# BlackIce_11_10_17.net
KiCad netlist of a schematic drawn in EAGLE
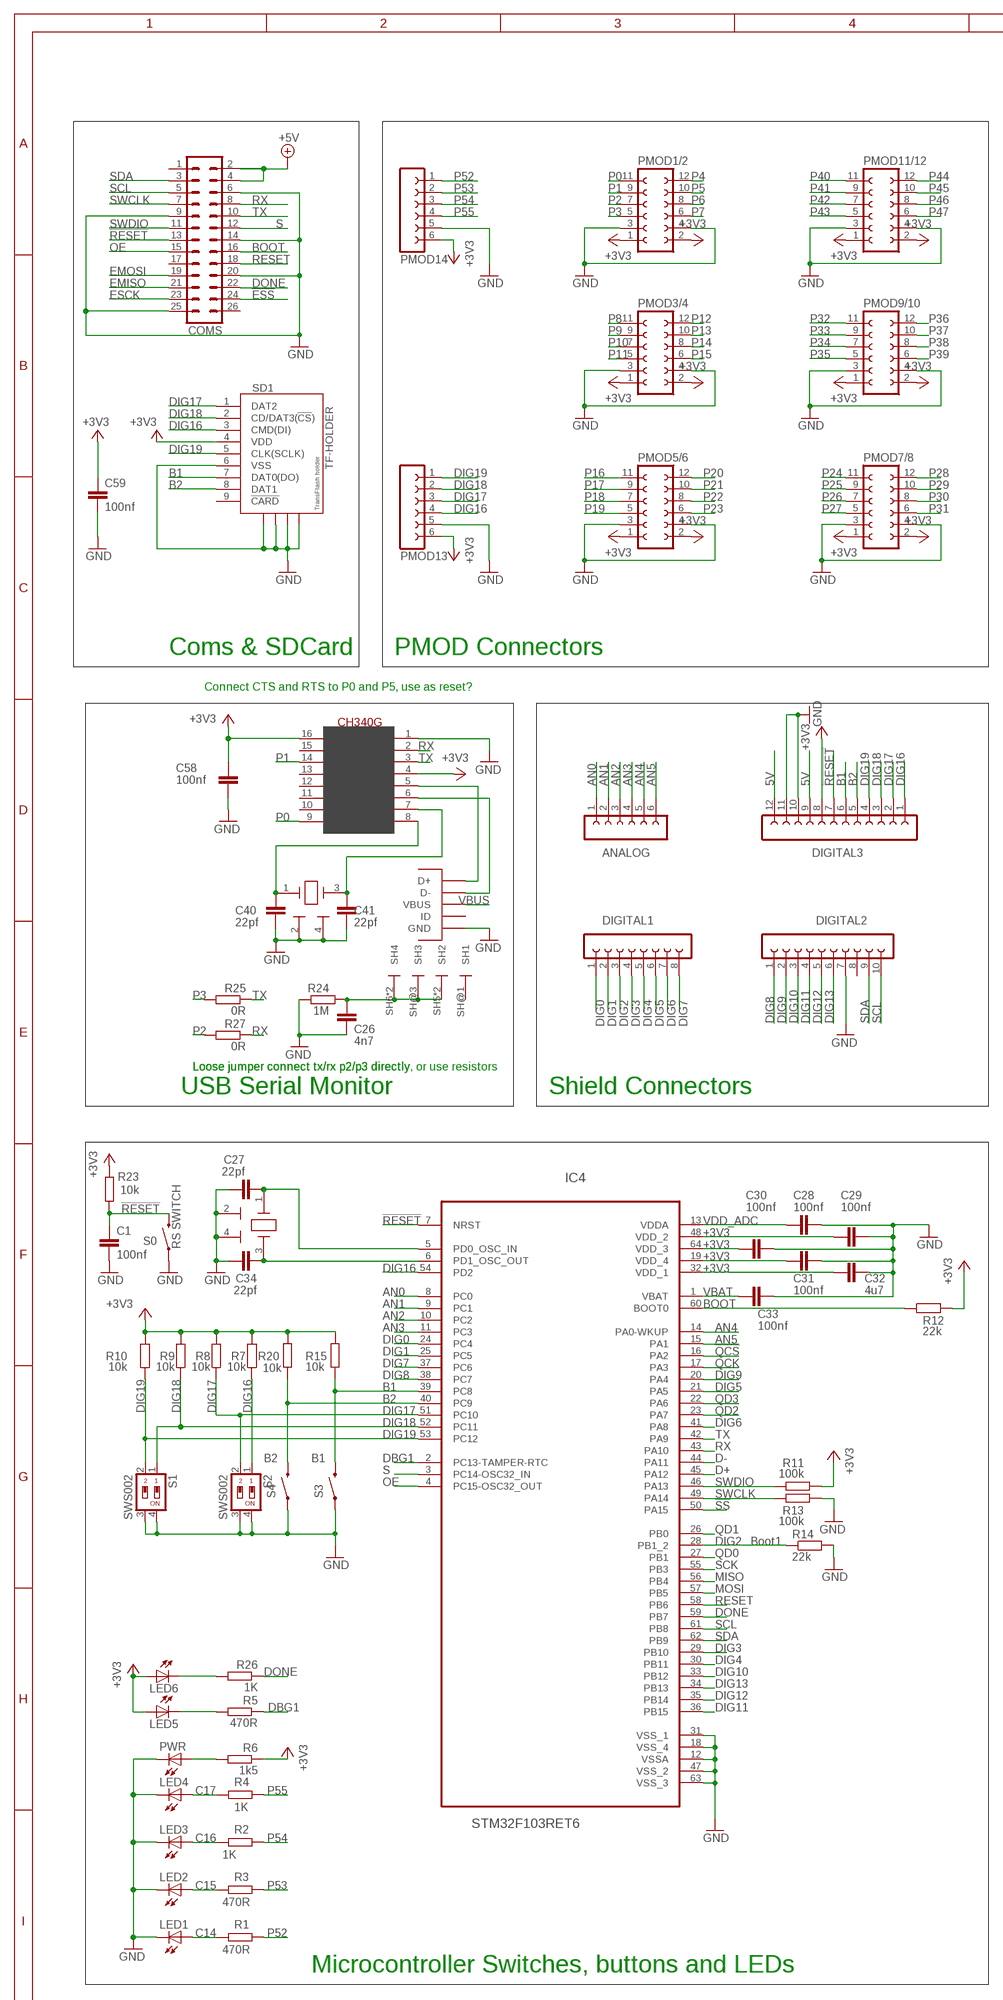
[diagram p0: schematic, sheet 1, part 1 of 2]
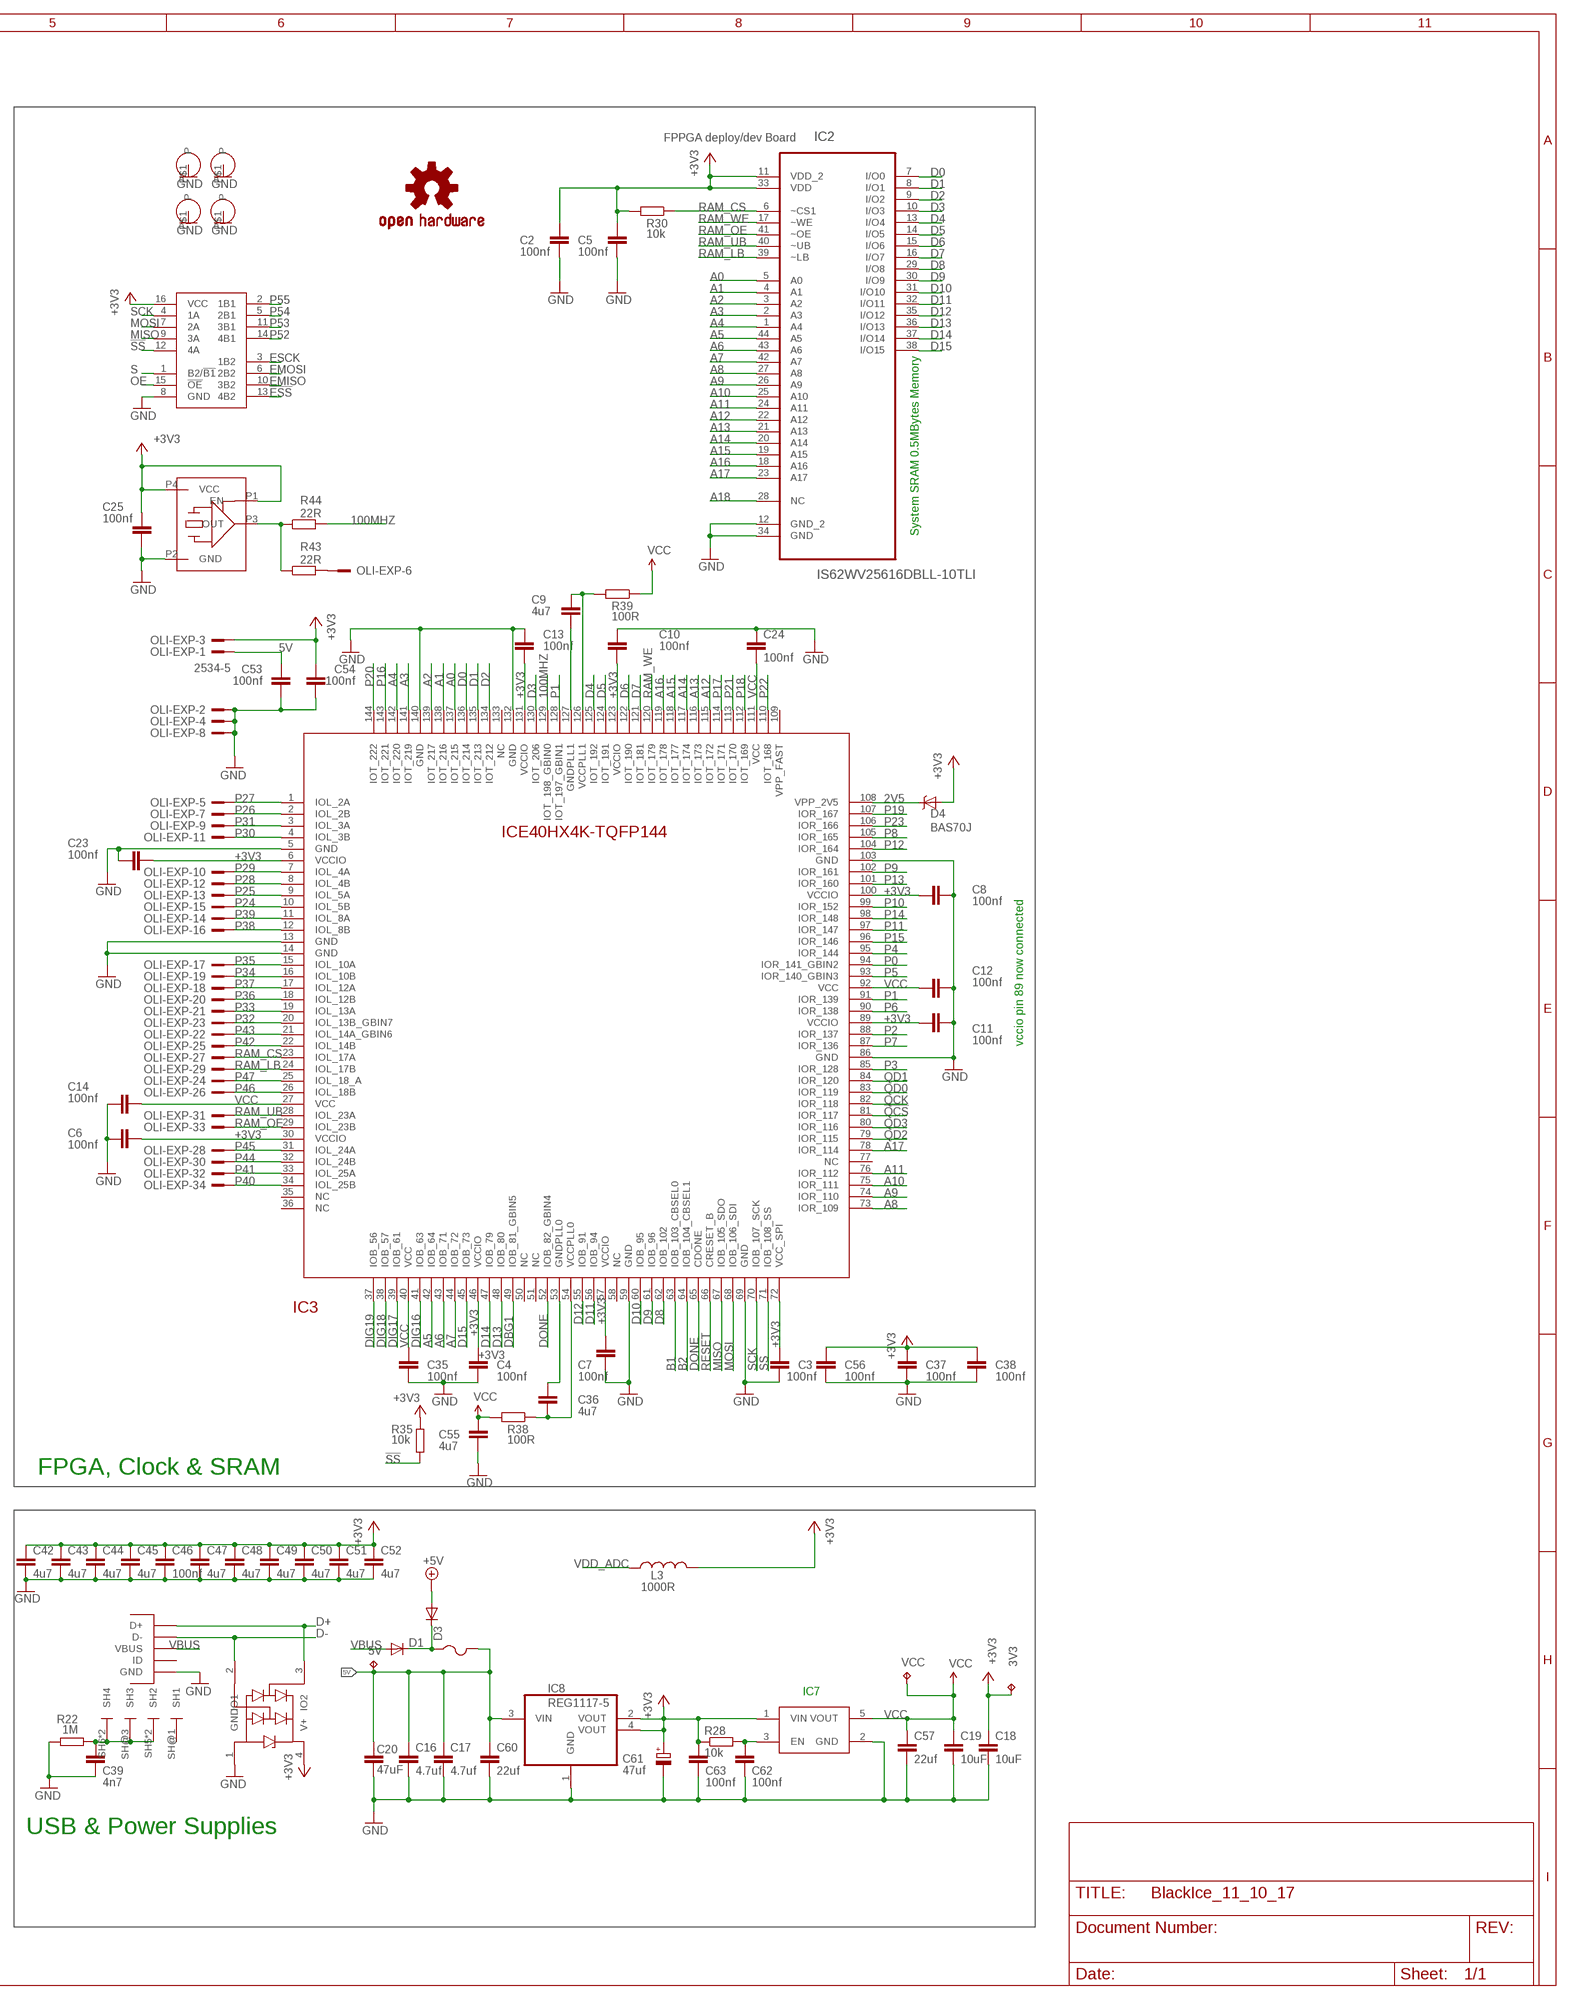
[diagram p1: schematic, sheet 1, part 2 of 2]

(export (version "E")
  (design (tool "Eeschema 10.0.6"))
  (components
    (comp (ref "3V3")
      (value "TPB1,27")
      (footprint "eagle-import:B1,27")
      (libsource (lib "eagle-import") (part "TPB1,27"))
    )
    (comp (ref "5V")
      (value "TPB1,27")
      (footprint "eagle-import:B1,27")
      (libsource (lib "eagle-import") (part "TPB1,27"))
    )
    (comp (ref "ANALOG")
      (value "FE06-1")
      (footprint "eagle-import:FE06")
      (libsource (lib "eagle-import") (part "FE06-1"))
    )
    (comp (ref "C1")
      (value "100nf")
      (footprint "eagle-import:C0402")
      (libsource (lib "eagle-import") (part "C-EUC0402"))
    )
    (comp (ref "C2")
      (value "100nf")
      (footprint "eagle-import:C0402")
      (libsource (lib "eagle-import") (part "C-EUC0402"))
    )
    (comp (ref "C3")
      (value "100nf")
      (footprint "eagle-import:C0402")
      (libsource (lib "eagle-import") (part "C-EUC0402"))
    )
    (comp (ref "C4")
      (value "100nf")
      (footprint "eagle-import:C0402")
      (libsource (lib "eagle-import") (part "C-EUC0402"))
    )
    (comp (ref "C5")
      (value "100nf")
      (footprint "eagle-import:C0402")
      (libsource (lib "eagle-import") (part "C-EUC0402"))
    )
    (comp (ref "C6")
      (value "100nf")
      (footprint "eagle-import:C0402")
      (libsource (lib "eagle-import") (part "C-EUC0402"))
    )
    (comp (ref "C7")
      (value "100nf")
      (footprint "eagle-import:C0402")
      (libsource (lib "eagle-import") (part "C-EUC0402"))
    )
    (comp (ref "C8")
      (value "100nf")
      (footprint "eagle-import:C0402")
      (libsource (lib "eagle-import") (part "C-EUC0402"))
    )
    (comp (ref "C9")
      (value "4u7")
      (footprint "eagle-import:C0402")
      (libsource (lib "eagle-import") (part "C-EUC0402"))
    )
    (comp (ref "C10")
      (value "100nf")
      (footprint "eagle-import:C0402")
      (libsource (lib "eagle-import") (part "C-EUC0402"))
    )
    (comp (ref "C11")
      (value "100nf")
      (footprint "eagle-import:C0402")
      (libsource (lib "eagle-import") (part "C-EUC0402"))
    )
    (comp (ref "C12")
      (value "100nf")
      (footprint "eagle-import:C0402")
      (libsource (lib "eagle-import") (part "C-EUC0402"))
    )
    (comp (ref "C13")
      (value "100nf")
      (footprint "eagle-import:C0402")
      (libsource (lib "eagle-import") (part "C-EUC0402"))
    )
    (comp (ref "C14")
      (value "100nf")
      (footprint "eagle-import:C0402")
      (libsource (lib "eagle-import") (part "C-EUC0402"))
    )
    (comp (ref "C16")
      (value "4.7uf")
      (footprint "eagle-import:C0402")
      (libsource (lib "eagle-import") (part "C-EUC0402"))
    )
    (comp (ref "C17")
      (value "4.7uf")
      (footprint "eagle-import:C0402")
      (libsource (lib "eagle-import") (part "C-EUC0402"))
    )
    (comp (ref "C18")
      (value "10uF")
      (footprint "eagle-import:C0603")
      (libsource (lib "eagle-import") (part "C-EUC0603"))
    )
    (comp (ref "C19")
      (value "10uF")
      (footprint "eagle-import:C0603")
      (libsource (lib "eagle-import") (part "C-EUC0603"))
    )
    (comp (ref "C20")
      (value "47uF")
      (footprint "eagle-import:1206")
      (libsource (lib "eagle-import") (part "C_1206"))
    )
    (comp (ref "C23")
      (value "100nf")
      (footprint "eagle-import:C0402")
      (libsource (lib "eagle-import") (part "C-EUC0402"))
    )
    (comp (ref "C24")
      (value "100nf")
      (footprint "eagle-import:C0402")
      (libsource (lib "eagle-import") (part "C-EUC0402"))
    )
    (comp (ref "C25")
      (value "100nf")
      (footprint "eagle-import:C0402")
      (libsource (lib "eagle-import") (part "C-EUC0402"))
    )
    (comp (ref "C26")
      (value "4n7")
      (footprint "eagle-import:C0402")
      (libsource (lib "eagle-import") (part "C-EUC0402"))
    )
    (comp (ref "C27")
      (value "22pf")
      (footprint "eagle-import:C0402")
      (libsource (lib "eagle-import") (part "C-EUC0402"))
    )
    (comp (ref "C28")
      (value "100nf")
      (footprint "eagle-import:C0402")
      (libsource (lib "eagle-import") (part "C-EUC0402"))
    )
    (comp (ref "C29")
      (value "100nf")
      (footprint "eagle-import:C0402")
      (libsource (lib "eagle-import") (part "C-EUC0402"))
    )
    (comp (ref "C30")
      (value "100nf")
      (footprint "eagle-import:C0402")
      (libsource (lib "eagle-import") (part "C-EUC0402"))
    )
    (comp (ref "C31")
      (value "100nf")
      (footprint "eagle-import:C0402")
      (libsource (lib "eagle-import") (part "C-EUC0402"))
    )
    (comp (ref "C32")
      (value "4u7")
      (footprint "eagle-import:C0402")
      (libsource (lib "eagle-import") (part "C-EUC0402"))
    )
    (comp (ref "C33")
      (value "100nf")
      (footprint "eagle-import:C0402")
      (libsource (lib "eagle-import") (part "C-EUC0402"))
    )
    (comp (ref "C34")
      (value "22pf")
      (footprint "eagle-import:C0402")
      (libsource (lib "eagle-import") (part "C-EUC0402"))
    )
    (comp (ref "C35")
      (value "100nf")
      (footprint "eagle-import:C0402")
      (libsource (lib "eagle-import") (part "C-EUC0402"))
    )
    (comp (ref "C36")
      (value "4u7")
      (footprint "eagle-import:C0402")
      (libsource (lib "eagle-import") (part "C-EUC0402"))
    )
    (comp (ref "C37")
      (value "100nf")
      (footprint "eagle-import:C0402")
      (libsource (lib "eagle-import") (part "C-EUC0402"))
    )
    (comp (ref "C38")
      (value "100nf")
      (footprint "eagle-import:C0402")
      (libsource (lib "eagle-import") (part "C-EUC0402"))
    )
    (comp (ref "C39")
      (value "4n7")
      (footprint "eagle-import:C0402")
      (libsource (lib "eagle-import") (part "C-EUC0402"))
    )
    (comp (ref "C40")
      (value "22pf")
      (footprint "eagle-import:C0402")
      (libsource (lib "eagle-import") (part "C-EUC0402"))
    )
    (comp (ref "C41")
      (value "22pf")
      (footprint "eagle-import:C0402")
      (libsource (lib "eagle-import") (part "C-EUC0402"))
    )
    (comp (ref "C42")
      (value "4u7")
      (footprint "eagle-import:C0402")
      (libsource (lib "eagle-import") (part "C-EUC0402"))
    )
    (comp (ref "C43")
      (value "4u7")
      (footprint "eagle-import:C0402")
      (libsource (lib "eagle-import") (part "C-EUC0402"))
    )
    (comp (ref "C44")
      (value "4u7")
      (footprint "eagle-import:C0402")
      (libsource (lib "eagle-import") (part "C-EUC0402"))
    )
    (comp (ref "C45")
      (value "4u7")
      (footprint "eagle-import:C0402")
      (libsource (lib "eagle-import") (part "C-EUC0402"))
    )
    (comp (ref "C46")
      (value "100nf")
      (footprint "eagle-import:C0402")
      (libsource (lib "eagle-import") (part "C-EUC0402"))
    )
    (comp (ref "C47")
      (value "4u7")
      (footprint "eagle-import:C0402")
      (libsource (lib "eagle-import") (part "C-EUC0402"))
    )
    (comp (ref "C48")
      (value "4u7")
      (footprint "eagle-import:C0402")
      (libsource (lib "eagle-import") (part "C-EUC0402"))
    )
    (comp (ref "C49")
      (value "4u7")
      (footprint "eagle-import:C0402")
      (libsource (lib "eagle-import") (part "C-EUC0402"))
    )
    (comp (ref "C50")
      (value "4u7")
      (footprint "eagle-import:C0402")
      (libsource (lib "eagle-import") (part "C-EUC0402"))
    )
    (comp (ref "C51")
      (value "4u7")
      (footprint "eagle-import:C0402")
      (libsource (lib "eagle-import") (part "C-EUC0402"))
    )
    (comp (ref "C52")
      (value "4u7")
      (footprint "eagle-import:C0402")
      (libsource (lib "eagle-import") (part "C-EUC0402"))
    )
    (comp (ref "C53")
      (value "100nf")
      (footprint "eagle-import:C0402")
      (libsource (lib "eagle-import") (part "C-EUC0402"))
    )
    (comp (ref "C54")
      (value "100nf")
      (footprint "eagle-import:C0402")
      (libsource (lib "eagle-import") (part "C-EUC0402"))
    )
    (comp (ref "C55")
      (value "4u7")
      (footprint "eagle-import:C0402")
      (libsource (lib "eagle-import") (part "C-EUC0402"))
    )
    (comp (ref "C56")
      (value "100nf")
      (footprint "eagle-import:C0402")
      (libsource (lib "eagle-import") (part "C-EUC0402"))
    )
    (comp (ref "C57")
      (value "22uf")
      (footprint "eagle-import:C0603")
      (libsource (lib "eagle-import") (part "C-EUC0603"))
    )
    (comp (ref "C58")
      (value "100nf")
      (footprint "eagle-import:C0402")
      (libsource (lib "eagle-import") (part "C-EUC0402"))
    )
    (comp (ref "C59")
      (value "100nf")
      (footprint "eagle-import:C0402")
      (libsource (lib "eagle-import") (part "C-EUC0402"))
    )
    (comp (ref "C60")
      (value "22uf")
      (footprint "eagle-import:C0603")
      (libsource (lib "eagle-import") (part "C-EUC0603"))
    )
    (comp (ref "C61")
      (value "47uf")
      (footprint "eagle-import:R_2012-12W")
      (libsource (lib "eagle-import") (part "CPOL-EUR/2012-12W"))
    )
    (comp (ref "C62")
      (value "100nf")
      (footprint "eagle-import:C0402")
      (libsource (lib "eagle-import") (part "C-EUC0402"))
    )
    (comp (ref "C63")
      (value "100nf")
      (footprint "eagle-import:C0402")
      (libsource (lib "eagle-import") (part "C-EUC0402"))
    )
    (comp (ref "COM")
      (value "FCI-MICROUSB-B-PEG")
      (footprint "eagle-import:MICROUSB-B-PEG")
      (libsource (lib "eagle-import") (part "FCI-MICROUSB-B-PEG"))
    )
    (comp (ref "COMS")
      (value "MA13-2")
      (footprint "eagle-import:MA13-2")
      (libsource (lib "eagle-import") (part "MA13-2"))
    )
    (comp (ref "D1")
      (value "DIODE-SOD123")
      (footprint "eagle-import:SOD123")
      (libsource (lib "eagle-import") (part "DIODE-SOD123"))
    )
    (comp (ref "D3")
      (value "DIODE-SOD123")
      (footprint "eagle-import:SOD123")
      (libsource (lib "eagle-import") (part "DIODE-SOD123"))
    )
    (comp (ref "D4")
      (value "BAS70J")
      (footprint "eagle-import:SOD-323")
      (libsource (lib "eagle-import") (part "BAS70J"))
    )
    (comp (ref "DIGITAL1")
      (value "FE08-1")
      (footprint "eagle-import:FE08")
      (libsource (lib "eagle-import") (part "FE08-1"))
    )
    (comp (ref "DIGITAL2")
      (value "FE10-1")
      (footprint "eagle-import:FE10")
      (libsource (lib "eagle-import") (part "FE10-1"))
    )
    (comp (ref "DIGITAL3")
      (value "FE12-1")
      (footprint "eagle-import:FE12")
      (libsource (lib "eagle-import") (part "FE12-1"))
    )
    (comp (ref "ESD1")
      (value "PRTR5V0U2X")
      (footprint "eagle-import:SOT143B")
      (libsource (lib "eagle-import") (part "PRTR5V0U2X"))
    )
    (comp (ref "F1")
      (value "PTCFUSE-1206")
      (footprint "eagle-import:R1206")
      (libsource (lib "eagle-import") (part "PTCFUSE-1206"))
    )
    (comp (ref "IC1")
      (value "CH340G")
      (footprint "eagle-import:SOIC16")
      (libsource (lib "eagle-import") (part "CH340G"))
    )
    (comp (ref "IC2")
      (value "IS62WV25616DBLL-10TLI")
      (footprint "eagle-import:SOP80P1176X120-44N")
      (fields (field (name "MPN") "IS62WV25616DBLL-45TLI"))
      (libsource (lib "eagle-import") (part "IS62WV25616DBLL-45TLI"))
    )
    (comp (ref "IC3")
      (value "ICE40HX4K_TQFP144")
      (footprint "eagle-import:TQFP144")
      (libsource (lib "eagle-import") (part "ICE40HX4K_TQFP144"))
    )
    (comp (ref "IC4")
      (value "STM32F103RET6")
      (footprint "eagle-import:QFP50P1200X1200X160-64N")
      (libsource (lib "eagle-import") (part "STM32F103RET6"))
    )
    (comp (ref "IC6")
      (value "74CBTLV3257")
      (footprint "eagle-import:TSSOP-16")
      (libsource (lib "eagle-import") (part "74CBTLV3257"))
    )
    (comp (ref "IC7")
      (value "NCP114")
      (footprint "eagle-import:TSOP-5_SOT23-5")
      (libsource (lib "eagle-import") (part "NCP114"))
    )
    (comp (ref "IC8")
      (value "REG1117-5")
      (footprint "eagle-import:SOT223")
      (libsource (lib "eagle-import") (part "REG1117-5"))
    )
    (comp (ref "L3")
      (value "1000R")
      (footprint "eagle-import:C0402")
      (libsource (lib "eagle-import") (part "INDUCTOR0402"))
    )
    (comp (ref "LED1")
      (value "LEDCHIPLED_0603")
      (footprint "eagle-import:CHIPLED_0603")
      (libsource (lib "eagle-import") (part "LEDCHIPLED_0603"))
    )
    (comp (ref "LED2")
      (value "LEDCHIPLED_0603")
      (footprint "eagle-import:CHIPLED_0603")
      (libsource (lib "eagle-import") (part "LEDCHIPLED_0603"))
    )
    (comp (ref "LED3")
      (value "LEDCHIPLED_0603")
      (footprint "eagle-import:CHIPLED_0603")
      (libsource (lib "eagle-import") (part "LEDCHIPLED_0603"))
    )
    (comp (ref "LED4")
      (value "LEDCHIPLED_0603")
      (footprint "eagle-import:CHIPLED_0603")
      (libsource (lib "eagle-import") (part "LEDCHIPLED_0603"))
    )
    (comp (ref "LED5")
      (value "LEDCHIPLED_0603")
      (footprint "eagle-import:CHIPLED_0603")
      (libsource (lib "eagle-import") (part "LEDCHIPLED_0603"))
    )
    (comp (ref "LED6")
      (value "LEDCHIPLED_0603")
      (footprint "eagle-import:CHIPLED_0603")
      (libsource (lib "eagle-import") (part "LEDCHIPLED_0603"))
    )
    (comp (ref "OLI-EXP")
      (value "2534-5")
      (footprint "eagle-import:PAK100_2500-5-34")
      (libsource (lib "eagle-import") (part "2534-5"))
    )
    (comp (ref "OSHW")
      (value "OSHW-LOGOL")
      (footprint "eagle-import:OSHW-LOGO-L")
      (libsource (lib "eagle-import") (part "OSHW-LOGOL"))
    )
    (comp (ref "PMOD1/2")
      (value "FE06-2W")
      (footprint "eagle-import:FE06-2W")
      (libsource (lib "eagle-import") (part "FE06-2W"))
    )
    (comp (ref "PMOD3/4")
      (value "FE06-2W")
      (footprint "eagle-import:FE06-2W")
      (libsource (lib "eagle-import") (part "FE06-2W"))
    )
    (comp (ref "PMOD5/6")
      (value "FE06-2W")
      (footprint "eagle-import:FE06-2W")
      (libsource (lib "eagle-import") (part "FE06-2W"))
    )
    (comp (ref "PMOD7/8")
      (value "FE06-2W")
      (footprint "eagle-import:FE06-2W")
      (libsource (lib "eagle-import") (part "FE06-2W"))
    )
    (comp (ref "PMOD9/10")
      (value "FE06-2W")
      (footprint "eagle-import:FE06-2W")
      (libsource (lib "eagle-import") (part "FE06-2W"))
    )
    (comp (ref "PMOD11/12")
      (value "FE06-2W")
      (footprint "eagle-import:FE06-2W")
      (libsource (lib "eagle-import") (part "FE06-2W"))
    )
    (comp (ref "PMOD13")
      (value "FE06W")
      (footprint "eagle-import:FE06W")
      (libsource (lib "eagle-import") (part "FE06W"))
    )
    (comp (ref "PMOD14")
      (value "FE06W")
      (footprint "eagle-import:FE06W")
      (libsource (lib "eagle-import") (part "FE06W"))
    )
    (comp (ref "PWR")
      (value "LEDCHIPLED_0603")
      (footprint "eagle-import:CHIPLED_0603")
      (libsource (lib "eagle-import") (part "LEDCHIPLED_0603"))
    )
    (comp (ref "R1")
      (value "470R")
      (footprint "eagle-import:R0402")
      (libsource (lib "eagle-import") (part "resistor_R-EU_R0402"))
    )
    (comp (ref "R2")
      (value "1K")
      (footprint "eagle-import:R0402")
      (libsource (lib "eagle-import") (part "resistor_R-EU_R0402"))
    )
    (comp (ref "R3")
      (value "470R")
      (footprint "eagle-import:R0402")
      (libsource (lib "eagle-import") (part "resistor_R-EU_R0402"))
    )
    (comp (ref "R4")
      (value "1K")
      (footprint "eagle-import:R0402")
      (libsource (lib "eagle-import") (part "resistor_R-EU_R0402"))
    )
    (comp (ref "R5")
      (value "470R")
      (footprint "eagle-import:R0402")
      (libsource (lib "eagle-import") (part "resistor_R-EU_R0402"))
    )
    (comp (ref "R6")
      (value "1k5")
      (footprint "eagle-import:R0402")
      (libsource (lib "eagle-import") (part "resistor_R-EU_R0402"))
    )
    (comp (ref "R7")
      (value "10k")
      (footprint "eagle-import:R0402")
      (libsource (lib "eagle-import") (part "resistor_R-EU_R0402"))
    )
    (comp (ref "R8")
      (value "10k")
      (footprint "eagle-import:R0402")
      (libsource (lib "eagle-import") (part "resistor_R-EU_R0402"))
    )
    (comp (ref "R9")
      (value "10k")
      (footprint "eagle-import:R0402")
      (libsource (lib "eagle-import") (part "resistor_R-EU_R0402"))
    )
    (comp (ref "R10")
      (value "10k")
      (footprint "eagle-import:R0402")
      (libsource (lib "eagle-import") (part "resistor_R-EU_R0402"))
    )
    (comp (ref "R11")
      (value "100k")
      (footprint "eagle-import:R0402")
      (libsource (lib "eagle-import") (part "resistor_R-EU_R0402"))
    )
    (comp (ref "R12")
      (value "22k")
      (footprint "eagle-import:R0402")
      (libsource (lib "eagle-import") (part "resistor_R-EU_R0402"))
    )
    (comp (ref "R13")
      (value "100k")
      (footprint "eagle-import:R0402")
      (libsource (lib "eagle-import") (part "resistor_R-EU_R0402"))
    )
    (comp (ref "R14")
      (value "22k")
      (footprint "eagle-import:R0402")
      (libsource (lib "eagle-import") (part "resistor_R-EU_R0402"))
    )
    (comp (ref "R15")
      (value "10k")
      (footprint "eagle-import:R0402")
      (libsource (lib "eagle-import") (part "resistor_R-EU_R0402"))
    )
    (comp (ref "R20")
      (value "10k")
      (footprint "eagle-import:R0402")
      (libsource (lib "eagle-import") (part "resistor_R-EU_R0402"))
    )
    (comp (ref "R22")
      (value "1M")
      (footprint "eagle-import:R0402")
      (libsource (lib "eagle-import") (part "resistor_R-EU_R0402"))
    )
    (comp (ref "R23")
      (value "10k")
      (footprint "eagle-import:R0402")
      (libsource (lib "eagle-import") (part "R-EU_R0402"))
    )
    (comp (ref "R24")
      (value "1M")
      (footprint "eagle-import:R0402")
      (libsource (lib "eagle-import") (part "resistor_R-EU_R0402"))
    )
    (comp (ref "R25")
      (value "0R")
      (footprint "eagle-import:R0402")
      (libsource (lib "eagle-import") (part "resistor_R-EU_R0402"))
    )
    (comp (ref "R26")
      (value "1K")
      (footprint "eagle-import:R0402")
      (libsource (lib "eagle-import") (part "resistor_R-EU_R0402"))
    )
    (comp (ref "R27")
      (value "0R")
      (footprint "eagle-import:R0402")
      (libsource (lib "eagle-import") (part "resistor_R-EU_R0402"))
    )
    (comp (ref "R28")
      (value "10k")
      (footprint "eagle-import:R0402")
      (libsource (lib "eagle-import") (part "resistor_R-EU_R0402"))
    )
    (comp (ref "R30")
      (value "10k")
      (footprint "eagle-import:R0402")
      (libsource (lib "eagle-import") (part "resistor_R-EU_R0402"))
    )
    (comp (ref "R35")
      (value "10k")
      (footprint "eagle-import:R0402")
      (libsource (lib "eagle-import") (part "resistor_R-EU_R0402"))
    )
    (comp (ref "R38")
      (value "100R")
      (footprint "eagle-import:R0402")
      (libsource (lib "eagle-import") (part "resistor_R-EU_R0402"))
    )
    (comp (ref "R39")
      (value "100R")
      (footprint "eagle-import:R0402")
      (libsource (lib "eagle-import") (part "resistor_R-EU_R0402"))
    )
    (comp (ref "R43")
      (value "22R")
      (footprint "eagle-import:R0402")
      (libsource (lib "eagle-import") (part "resistor_R-EU_R0402"))
    )
    (comp (ref "R44")
      (value "22R")
      (footprint "eagle-import:R0402")
      (libsource (lib "eagle-import") (part "resistor_R-EU_R0402"))
    )
    (comp (ref "S0")
      (value "RS SWITCH")
      (footprint "eagle-import:TACTILE-SWITCH-1101NE")
      (libsource (lib "eagle-import") (part "SWITCH-MOMENTARY-2SMD-1101NE"))
    )
    (comp (ref "S1")
      (value "SWS002")
      (footprint "eagle-import:SMS-002")
      (libsource (lib "eagle-import") (part "SWS002"))
    )
    (comp (ref "S2")
      (value "SWS002")
      (footprint "eagle-import:SMS-002")
      (libsource (lib "eagle-import") (part "SWS002"))
    )
    (comp (ref "S3")
      (value "SWITCH-MOMENTARY-2SMD-1101NE")
      (footprint "eagle-import:TACTILE-SWITCH-1101NE")
      (libsource (lib "eagle-import") (part "SWITCH-MOMENTARY-2SMD-1101NE"))
    )
    (comp (ref "S4")
      (value "SWITCH-MOMENTARY-2SMD-1101NE")
      (footprint "eagle-import:TACTILE-SWITCH-1101NE")
      (libsource (lib "eagle-import") (part "SWITCH-MOMENTARY-2SMD-1101NE"))
    )
    (comp (ref "SD1")
      (value "TF-HOLDER")
      (footprint "eagle-import:TF-PULL")
      (libsource (lib "eagle-import") (part "TF-HOLDER"))
    )
    (comp (ref "U$2")
      (value "FCI-MICROUSB-B-PEG")
      (footprint "eagle-import:MICROUSB-B-PEG")
      (libsource (lib "eagle-import") (part "FCI-MICROUSB-B-PEG"))
    )
    (comp (ref "U$16")
      (value "HOLE-2.5MM")
      (footprint "eagle-import:2.5MM-HOLE")
      (libsource (lib "eagle-import") (part "HOLE-2.5MM"))
    )
    (comp (ref "U$21")
      (value "HOLE-2.5MM")
      (footprint "eagle-import:2.5MM-HOLE")
      (libsource (lib "eagle-import") (part "HOLE-2.5MM"))
    )
    (comp (ref "U$22")
      (value "HOLE-2.5MM")
      (footprint "eagle-import:2.5MM-HOLE")
      (libsource (lib "eagle-import") (part "HOLE-2.5MM"))
    )
    (comp (ref "U$24")
      (value "HOLE-2.5MM")
      (footprint "eagle-import:2.5MM-HOLE")
      (libsource (lib "eagle-import") (part "HOLE-2.5MM"))
    )
    (comp (ref "VCC")
      (value "TPB1,27")
      (footprint "eagle-import:B1,27")
      (libsource (lib "eagle-import") (part "TPB1,27"))
    )
    (comp (ref "X1")
      (value "TXC-7W-20.000MBB-T")
      (footprint "eagle-import:XTAL-7X5")
      (libsource (lib "eagle-import") (part "TXC-7W-20.000MBB-T"))
    )
    (comp (ref "Y1")
      (value "12MZ")
      (footprint "eagle-import:CRYSTAL-3.2X2.5")
      (libsource (lib "eagle-import") (part "7M-25"))
    )
    (comp (ref "Y2")
      (value "12Mz")
      (footprint "eagle-import:CRYSTAL-3.2X2.5")
      (libsource (lib "eagle-import") (part "7M-25"))
    )
  )
  (nets
    (net (code "1") (name "+3V3") (class "Default")
      (node (ref "3V3") (pin "TP") (pinfunction "TP_TP") (pintype "input"))
      (node (ref "C10") (pin "2") (pinfunction "2_2") (pintype "passive"))
      (node (ref "C11") (pin "1") (pinfunction "1_1") (pintype "passive"))
      (node (ref "C13") (pin "1") (pinfunction "1_1") (pintype "passive"))
      (node (ref "C18") (pin "1") (pinfunction "1_1") (pintype "passive"))
      (node (ref "C2") (pin "1") (pinfunction "1_1") (pintype "passive"))
      (node (ref "C23") (pin "1") (pinfunction "1_1") (pintype "passive"))
      (node (ref "C25") (pin "2") (pinfunction "2_2") (pintype "passive"))
      (node (ref "C29") (pin "2") (pinfunction "2_2") (pintype "passive"))
      (node (ref "C3") (pin "1") (pinfunction "1_1") (pintype "passive"))
      (node (ref "C30") (pin "2") (pinfunction "2_2") (pintype "passive"))
      (node (ref "C31") (pin "2") (pinfunction "2_2") (pintype "passive"))
      (node (ref "C32") (pin "2") (pinfunction "2_2") (pintype "passive"))
      (node (ref "C37") (pin "1") (pinfunction "1_1") (pintype "passive"))
      (node (ref "C38") (pin "1") (pinfunction "1_1") (pintype "passive"))
      (node (ref "C4") (pin "1") (pinfunction "1_1") (pintype "passive"))
      (node (ref "C42") (pin "1") (pinfunction "1_1") (pintype "passive"))
      (node (ref "C43") (pin "1") (pinfunction "1_1") (pintype "passive"))
      (node (ref "C44") (pin "1") (pinfunction "1_1") (pintype "passive"))
      (node (ref "C45") (pin "1") (pinfunction "1_1") (pintype "passive"))
      (node (ref "C46") (pin "1") (pinfunction "1_1") (pintype "passive"))
      (node (ref "C47") (pin "1") (pinfunction "1_1") (pintype "passive"))
      (node (ref "C48") (pin "1") (pinfunction "1_1") (pintype "passive"))
      (node (ref "C49") (pin "1") (pinfunction "1_1") (pintype "passive"))
      (node (ref "C5") (pin "1") (pinfunction "1_1") (pintype "passive"))
      (node (ref "C50") (pin "1") (pinfunction "1_1") (pintype "passive"))
      (node (ref "C51") (pin "1") (pinfunction "1_1") (pintype "passive"))
      (node (ref "C52") (pin "1") (pinfunction "1_1") (pintype "passive"))
      (node (ref "C54") (pin "1") (pinfunction "1_1") (pintype "passive"))
      (node (ref "C56") (pin "1") (pinfunction "1_1") (pintype "passive"))
      (node (ref "C58") (pin "2") (pinfunction "2_2") (pintype "passive"))
      (node (ref "C59") (pin "1") (pinfunction "1_1") (pintype "passive"))
      (node (ref "C6") (pin "2") (pinfunction "2_2") (pintype "passive"))
      (node (ref "C61") (pin "+") (pinfunction "+_+") (pintype "passive"))
      (node (ref "C63") (pin "2") (pinfunction "2_2") (pintype "passive"))
      (node (ref "C7") (pin "1") (pinfunction "1_1") (pintype "passive"))
      (node (ref "C8") (pin "1") (pinfunction "1_1") (pintype "passive"))
      (node (ref "D4") (pin "A") (pinfunction "A_A") (pintype "passive"))
      (node (ref "DIGITAL3") (pin "8") (pinfunction "8_8") (pintype "passive"))
      (node (ref "ESD1") (pin "4") (pinfunction "V+_4") (pintype "bidirectional"))
      (node (ref "IC1") (pin "16") (pinfunction "VCC_16") (pintype "bidirectional"))
      (node (ref "IC1") (pin "4") (pinfunction "V3_4") (pintype "bidirectional"))
      (node (ref "IC2") (pin "11") (pinfunction "VDD_2_11") (pintype "power_in"))
      (node (ref "IC2") (pin "33") (pinfunction "VDD_33") (pintype "power_in"))
      (node (ref "IC3") (pin "100") (pinfunction "VCCIO_100") (pintype "bidirectional"))
      (node (ref "IC3") (pin "123") (pinfunction "VCCIO_123") (pintype "bidirectional"))
      (node (ref "IC3") (pin "131") (pinfunction "VCCIO_131") (pintype "bidirectional"))
      (node (ref "IC3") (pin "30") (pinfunction "VCCIO_30") (pintype "bidirectional"))
      (node (ref "IC3") (pin "46") (pinfunction "VCCIO_46") (pintype "bidirectional"))
      (node (ref "IC3") (pin "57") (pinfunction "VCCIO_57") (pintype "bidirectional"))
      (node (ref "IC3") (pin "6") (pinfunction "VCCIO_6") (pintype "bidirectional"))
      (node (ref "IC3") (pin "72") (pinfunction "VCC_SPI_72") (pintype "bidirectional"))
      (node (ref "IC3") (pin "89") (pinfunction "VCCIO_89") (pintype "bidirectional"))
      (node (ref "IC4") (pin "19") (pinfunction "VDD_4_19") (pintype "power_in"))
      (node (ref "IC4") (pin "32") (pinfunction "VDD_1_32") (pintype "power_in"))
      (node (ref "IC4") (pin "48") (pinfunction "VDD_2_48") (pintype "power_in"))
      (node (ref "IC4") (pin "64") (pinfunction "VDD_3_64") (pintype "power_in"))
      (node (ref "IC6") (pin "16") (pinfunction "VCC_16") (pintype "power_in"))
      (node (ref "IC7") (pin "1") (pinfunction "VIN_1") (pintype "power_in"))
      (node (ref "IC8") (pin "2") (pinfunction "VOUT_2") (pintype "output"))
      (node (ref "IC8") (pin "4") (pinfunction "VOUT_4") (pintype "output"))
      (node (ref "L3") (pin "1") (pinfunction "1_1") (pintype "passive"))
      (node (ref "LED5") (pin "A") (pinfunction "A_A") (pintype "passive"))
      (node (ref "LED6") (pin "A") (pinfunction "A_A") (pintype "passive"))
      (node (ref "OLI-EXP") (pin "3") (pinfunction "KL_3") (pintype "passive"))
      (node (ref "PMOD1/2") (pin "1") (pinfunction "1_1") (pintype "passive"))
      (node (ref "PMOD1/2") (pin "2") (pinfunction "2_2") (pintype "passive"))
      (node (ref "PMOD11/12") (pin "1") (pinfunction "1_1") (pintype "passive"))
      (node (ref "PMOD11/12") (pin "2") (pinfunction "2_2") (pintype "passive"))
      (node (ref "PMOD13") (pin "6") (pinfunction "6_6") (pintype "passive"))
      (node (ref "PMOD14") (pin "6") (pinfunction "6_6") (pintype "passive"))
      (node (ref "PMOD3/4") (pin "1") (pinfunction "1_1") (pintype "passive"))
      (node (ref "PMOD3/4") (pin "2") (pinfunction "2_2") (pintype "passive"))
      (node (ref "PMOD5/6") (pin "1") (pinfunction "1_1") (pintype "passive"))
      (node (ref "PMOD5/6") (pin "2") (pinfunction "2_2") (pintype "passive"))
      (node (ref "PMOD7/8") (pin "1") (pinfunction "1_1") (pintype "passive"))
      (node (ref "PMOD7/8") (pin "2") (pinfunction "2_2") (pintype "passive"))
      (node (ref "PMOD9/10") (pin "1") (pinfunction "1_1") (pintype "passive"))
      (node (ref "PMOD9/10") (pin "2") (pinfunction "2_2") (pintype "passive"))
      (node (ref "R10") (pin "2") (pinfunction "2_2") (pintype "passive"))
      (node (ref "R11") (pin "1") (pinfunction "1_1") (pintype "passive"))
      (node (ref "R12") (pin "2") (pinfunction "2_2") (pintype "passive"))
      (node (ref "R15") (pin "2") (pinfunction "2_2") (pintype "passive"))
      (node (ref "R20") (pin "2") (pinfunction "2_2") (pintype "passive"))
      (node (ref "R23") (pin "2") (pinfunction "2_2") (pintype "passive"))
      (node (ref "R28") (pin "1") (pinfunction "1_1") (pintype "passive"))
      (node (ref "R30") (pin "2") (pinfunction "2_2") (pintype "passive"))
      (node (ref "R35") (pin "1") (pinfunction "1_1") (pintype "passive"))
      (node (ref "R6") (pin "1") (pinfunction "1_1") (pintype "passive"))
      (node (ref "R7") (pin "2") (pinfunction "2_2") (pintype "passive"))
      (node (ref "R8") (pin "2") (pinfunction "2_2") (pintype "passive"))
      (node (ref "R9") (pin "2") (pinfunction "2_2") (pintype "passive"))
      (node (ref "SD1") (pin "4") (pinfunction "VDD_4") (pintype "power_in"))
      (node (ref "X1") (pin "P1") (pinfunction "EN_P1") (pintype "input"))
      (node (ref "X1") (pin "P4") (pinfunction "VCC_P4") (pintype "power_in"))
    )
    (net (code "2") (name "+5V") (class "Default")
      (node (ref "COMS") (pin "2") (pinfunction "2_2") (pintype "passive"))
      (node (ref "COMS") (pin "4") (pinfunction "4_4") (pintype "passive"))
      (node (ref "D3") (pin "A") (pinfunction "A_A") (pintype "passive"))
    )
    (net (code "3") (name "/2V5") (class "Default")
      (node (ref "D4") (pin "C") (pinfunction "C_C") (pintype "passive"))
      (node (ref "IC3") (pin "108") (pinfunction "VPP_2V5_108") (pintype "bidirectional"))
    )
    (net (code "4") (name "/100MHZ") (class "Default")
      (node (ref "IC3") (pin "129") (pinfunction "IOT_198_GBIN0_129") (pintype "bidirectional"))
      (node (ref "R44") (pin "2") (pinfunction "2_2") (pintype "passive"))
    )
    (net (code "5") (name "/A0") (class "Default")
      (node (ref "IC2") (pin "5") (pinfunction "A0_5") (pintype "input"))
      (node (ref "IC3") (pin "137") (pinfunction "IOT_215_137") (pintype "bidirectional"))
    )
    (net (code "6") (name "/A1") (class "Default")
      (node (ref "IC2") (pin "4") (pinfunction "A1_4") (pintype "input"))
      (node (ref "IC3") (pin "138") (pinfunction "IOT_216_138") (pintype "bidirectional"))
    )
    (net (code "7") (name "/A2") (class "Default")
      (node (ref "IC2") (pin "3") (pinfunction "A2_3") (pintype "input"))
      (node (ref "IC3") (pin "139") (pinfunction "IOT_217_139") (pintype "bidirectional"))
    )
    (net (code "8") (name "/A3") (class "Default")
      (node (ref "IC2") (pin "2") (pinfunction "A3_2") (pintype "input"))
      (node (ref "IC3") (pin "141") (pinfunction "IOT_219_141") (pintype "bidirectional"))
    )
    (net (code "9") (name "/A4") (class "Default")
      (node (ref "IC2") (pin "1") (pinfunction "A4_1") (pintype "input"))
      (node (ref "IC3") (pin "142") (pinfunction "IOT_220_142") (pintype "bidirectional"))
    )
    (net (code "10") (name "/A5") (class "Default")
      (node (ref "IC2") (pin "44") (pinfunction "A5_44") (pintype "input"))
      (node (ref "IC3") (pin "42") (pinfunction "IOB_64_42") (pintype "bidirectional"))
    )
    (net (code "11") (name "/A6") (class "Default")
      (node (ref "IC2") (pin "43") (pinfunction "A6_43") (pintype "input"))
      (node (ref "IC3") (pin "43") (pinfunction "IOB_71_43") (pintype "bidirectional"))
    )
    (net (code "12") (name "/A7") (class "Default")
      (node (ref "IC2") (pin "42") (pinfunction "A7_42") (pintype "input"))
      (node (ref "IC3") (pin "44") (pinfunction "IOB_72_44") (pintype "bidirectional"))
    )
    (net (code "13") (name "/A8") (class "Default")
      (node (ref "IC2") (pin "27") (pinfunction "A8_27") (pintype "input"))
      (node (ref "IC3") (pin "73") (pinfunction "IOR_109_73") (pintype "bidirectional"))
    )
    (net (code "14") (name "/A9") (class "Default")
      (node (ref "IC2") (pin "26") (pinfunction "A9_26") (pintype "input"))
      (node (ref "IC3") (pin "74") (pinfunction "IOR_110_74") (pintype "bidirectional"))
    )
    (net (code "15") (name "/A10") (class "Default")
      (node (ref "IC2") (pin "25") (pinfunction "A10_25") (pintype "input"))
      (node (ref "IC3") (pin "75") (pinfunction "IOR_111_75") (pintype "bidirectional"))
    )
    (net (code "16") (name "/A11") (class "Default")
      (node (ref "IC2") (pin "24") (pinfunction "A11_24") (pintype "input"))
      (node (ref "IC3") (pin "76") (pinfunction "IOR_112_76") (pintype "bidirectional"))
    )
    (net (code "17") (name "/A12") (class "Default")
      (node (ref "IC2") (pin "22") (pinfunction "A12_22") (pintype "input"))
      (node (ref "IC3") (pin "115") (pinfunction "IOT_172_115") (pintype "bidirectional"))
    )
    (net (code "18") (name "/A13") (class "Default")
      (node (ref "IC2") (pin "21") (pinfunction "A13_21") (pintype "input"))
      (node (ref "IC3") (pin "116") (pinfunction "IOT_173_116") (pintype "bidirectional"))
    )
    (net (code "19") (name "/A14") (class "Default")
      (node (ref "IC2") (pin "20") (pinfunction "A14_20") (pintype "input"))
      (node (ref "IC3") (pin "117") (pinfunction "IOT_174_117") (pintype "bidirectional"))
    )
    (net (code "20") (name "/A15") (class "Default")
      (node (ref "IC2") (pin "19") (pinfunction "A15_19") (pintype "input"))
      (node (ref "IC3") (pin "118") (pinfunction "IOT_177_118") (pintype "bidirectional"))
    )
    (net (code "21") (name "/A16") (class "Default")
      (node (ref "IC2") (pin "18") (pinfunction "A16_18") (pintype "input"))
      (node (ref "IC3") (pin "119") (pinfunction "IOT_178_119") (pintype "bidirectional"))
    )
    (net (code "22") (name "/A17") (class "Default")
      (node (ref "IC2") (pin "23") (pinfunction "A17_23") (pintype "input"))
      (node (ref "IC3") (pin "78") (pinfunction "IOR_114_78") (pintype "bidirectional"))
    )
    (net (code "24") (name "/AN0") (class "Default")
      (node (ref "ANALOG") (pin "1") (pinfunction "1_1") (pintype "passive"))
      (node (ref "IC4") (pin "8") (pinfunction "PC0_8") (pintype "bidirectional"))
    )
    (net (code "25") (name "/AN1") (class "Default")
      (node (ref "ANALOG") (pin "2") (pinfunction "2_2") (pintype "passive"))
      (node (ref "IC4") (pin "9") (pinfunction "PC1_9") (pintype "bidirectional"))
    )
    (net (code "26") (name "/AN2") (class "Default")
      (node (ref "ANALOG") (pin "3") (pinfunction "3_3") (pintype "passive"))
      (node (ref "IC4") (pin "10") (pinfunction "PC2_10") (pintype "bidirectional"))
    )
    (net (code "27") (name "/AN3") (class "Default")
      (node (ref "ANALOG") (pin "4") (pinfunction "4_4") (pintype "passive"))
      (node (ref "IC4") (pin "11") (pinfunction "PC3_11") (pintype "bidirectional"))
    )
    (net (code "28") (name "/AN4") (class "Default")
      (node (ref "ANALOG") (pin "5") (pinfunction "5_5") (pintype "passive"))
      (node (ref "IC4") (pin "14") (pinfunction "PA0-WKUP_14") (pintype "bidirectional"))
    )
    (net (code "29") (name "/AN5") (class "Default")
      (node (ref "ANALOG") (pin "6") (pinfunction "6_6") (pintype "passive"))
      (node (ref "IC4") (pin "15") (pinfunction "PA1_15") (pintype "bidirectional"))
    )
    (net (code "30") (name "/B1") (class "Default")
      (node (ref "DIGITAL3") (pin "6") (pinfunction "6_6") (pintype "passive"))
      (node (ref "IC3") (pin "63") (pinfunction "IOB_103_CBSEL0_63") (pintype "bidirectional"))
      (node (ref "IC4") (pin "39") (pinfunction "PC8_39") (pintype "bidirectional"))
      (node (ref "R15") (pin "1") (pinfunction "1_1") (pintype "passive"))
      (node (ref "S3") (pin "2") (pinfunction "2_2") (pintype "passive"))
      (node (ref "SD1") (pin "7") (pinfunction "DAT0(DO)_7") (pintype "bidirectional"))
    )
    (net (code "31") (name "/B2") (class "Default")
      (node (ref "DIGITAL3") (pin "5") (pinfunction "5_5") (pintype "passive"))
      (node (ref "IC3") (pin "64") (pinfunction "IOB_104_CBSEL1_64") (pintype "bidirectional"))
      (node (ref "IC4") (pin "40") (pinfunction "PC9_40") (pintype "bidirectional"))
      (node (ref "R20") (pin "1") (pinfunction "1_1") (pintype "passive"))
      (node (ref "S4") (pin "2") (pinfunction "2_2") (pintype "passive"))
      (node (ref "SD1") (pin "8") (pinfunction "DAT1_8") (pintype "bidirectional"))
    )
    (net (code "32") (name "/BOOT") (class "Default")
      (node (ref "COMS") (pin "16") (pinfunction "16_16") (pintype "passive"))
      (node (ref "IC4") (pin "60") (pinfunction "BOOT0_60") (pintype "passive"))
      (node (ref "R12") (pin "1") (pinfunction "1_1") (pintype "passive"))
    )
    (net (code "33") (name "/C14") (class "Default")
      (node (ref "LED1") (pin "A") (pinfunction "A_A") (pintype "passive"))
      (node (ref "R1") (pin "1") (pinfunction "1_1") (pintype "passive"))
    )
    (net (code "34") (name "/C15") (class "Default")
      (node (ref "LED2") (pin "A") (pinfunction "A_A") (pintype "passive"))
      (node (ref "R3") (pin "1") (pinfunction "1_1") (pintype "passive"))
    )
    (net (code "35") (name "/C16") (class "Default")
      (node (ref "LED3") (pin "A") (pinfunction "A_A") (pintype "passive"))
      (node (ref "R2") (pin "1") (pinfunction "1_1") (pintype "passive"))
    )
    (net (code "36") (name "/C17") (class "Default")
      (node (ref "LED4") (pin "A") (pinfunction "A_A") (pintype "passive"))
      (node (ref "R4") (pin "1") (pinfunction "1_1") (pintype "passive"))
    )
    (net (code "37") (name "/D+") (class "Default")
      (node (ref "ESD1") (pin "3") (pinfunction "IO2_3") (pintype "bidirectional"))
      (node (ref "IC4") (pin "45") (pinfunction "PA12_45") (pintype "bidirectional"))
      (node (ref "U$2") (pin "P$3") (pinfunction "D+_P$3") (pintype "bidirectional"))
    )
    (net (code "38") (name "/D-") (class "Default")
      (node (ref "ESD1") (pin "2") (pinfunction "IO1_2") (pintype "bidirectional"))
      (node (ref "IC4") (pin "44") (pinfunction "PA11_44") (pintype "bidirectional"))
      (node (ref "U$2") (pin "P$2") (pinfunction "D-_P$2") (pintype "bidirectional"))
    )
    (net (code "39") (name "/D0") (class "Default")
      (node (ref "IC2") (pin "7") (pinfunction "I/O0_7") (pintype "bidirectional"))
      (node (ref "IC3") (pin "136") (pinfunction "IOT_214_136") (pintype "bidirectional"))
    )
    (net (code "40") (name "/D1") (class "Default")
      (node (ref "IC2") (pin "8") (pinfunction "I/O1_8") (pintype "bidirectional"))
      (node (ref "IC3") (pin "135") (pinfunction "IOT_213_135") (pintype "bidirectional"))
    )
    (net (code "41") (name "/D2") (class "Default")
      (node (ref "IC2") (pin "9") (pinfunction "I/O2_9") (pintype "bidirectional"))
      (node (ref "IC3") (pin "134") (pinfunction "IOT_212_134") (pintype "bidirectional"))
    )
    (net (code "42") (name "/D3") (class "Default")
      (node (ref "IC2") (pin "10") (pinfunction "I/O3_10") (pintype "bidirectional"))
      (node (ref "IC3") (pin "130") (pinfunction "IOT_206_130") (pintype "bidirectional"))
    )
    (net (code "43") (name "/D4") (class "Default")
      (node (ref "IC2") (pin "13") (pinfunction "I/O4_13") (pintype "bidirectional"))
      (node (ref "IC3") (pin "125") (pinfunction "IOT_192_125") (pintype "bidirectional"))
    )
    (net (code "44") (name "/D5") (class "Default")
      (node (ref "IC2") (pin "14") (pinfunction "I/O5_14") (pintype "bidirectional"))
      (node (ref "IC3") (pin "124") (pinfunction "IOT_191_124") (pintype "bidirectional"))
    )
    (net (code "45") (name "/D6") (class "Default")
      (node (ref "IC2") (pin "15") (pinfunction "I/O6_15") (pintype "bidirectional"))
      (node (ref "IC3") (pin "122") (pinfunction "IOT_190_122") (pintype "bidirectional"))
    )
    (net (code "46") (name "/D7") (class "Default")
      (node (ref "IC2") (pin "16") (pinfunction "I/O7_16") (pintype "bidirectional"))
      (node (ref "IC3") (pin "121") (pinfunction "IOT_181_121") (pintype "bidirectional"))
    )
    (net (code "47") (name "/D8") (class "Default")
      (node (ref "IC2") (pin "29") (pinfunction "I/O8_29") (pintype "bidirectional"))
      (node (ref "IC3") (pin "62") (pinfunction "IOB_102_62") (pintype "bidirectional"))
    )
    (net (code "48") (name "/D9") (class "Default")
      (node (ref "IC2") (pin "30") (pinfunction "I/O9_30") (pintype "bidirectional"))
      (node (ref "IC3") (pin "61") (pinfunction "IOB_96_61") (pintype "bidirectional"))
    )
    (net (code "49") (name "/D10") (class "Default")
      (node (ref "IC2") (pin "31") (pinfunction "I/O10_31") (pintype "bidirectional"))
      (node (ref "IC3") (pin "60") (pinfunction "IOB_95_60") (pintype "bidirectional"))
    )
    (net (code "50") (name "/D11") (class "Default")
      (node (ref "IC2") (pin "32") (pinfunction "I/O11_32") (pintype "bidirectional"))
      (node (ref "IC3") (pin "56") (pinfunction "IOB_94_56") (pintype "bidirectional"))
    )
    (net (code "51") (name "/D12") (class "Default")
      (node (ref "IC2") (pin "35") (pinfunction "I/O12_35") (pintype "bidirectional"))
      (node (ref "IC3") (pin "55") (pinfunction "IOB_91_55") (pintype "bidirectional"))
    )
    (net (code "52") (name "/D13") (class "Default")
      (node (ref "IC2") (pin "36") (pinfunction "I/O13_36") (pintype "bidirectional"))
      (node (ref "IC3") (pin "48") (pinfunction "IOB_80_48") (pintype "bidirectional"))
    )
    (net (code "53") (name "/D14") (class "Default")
      (node (ref "IC2") (pin "37") (pinfunction "I/O14_37") (pintype "bidirectional"))
      (node (ref "IC3") (pin "47") (pinfunction "IOB_79_47") (pintype "bidirectional"))
    )
    (net (code "54") (name "/D15") (class "Default")
      (node (ref "IC2") (pin "38") (pinfunction "I/O15_38") (pintype "bidirectional"))
      (node (ref "IC3") (pin "45") (pinfunction "IOB_73_45") (pintype "bidirectional"))
    )
    (net (code "55") (name "/DBG1") (class "Default")
      (node (ref "IC3") (pin "49") (pinfunction "IOB_81_GBIN5_49") (pintype "bidirectional"))
      (node (ref "IC4") (pin "2") (pinfunction "PC13-TAMPER-RTC_2") (pintype "input"))
      (node (ref "R5") (pin "1") (pinfunction "1_1") (pintype "passive"))
    )
    (net (code "56") (name "/DIG0") (class "Default")
      (node (ref "DIGITAL1") (pin "1") (pinfunction "1_1") (pintype "passive"))
      (node (ref "IC4") (pin "24") (pinfunction "PC4_24") (pintype "passive"))
    )
    (net (code "57") (name "/DIG1") (class "Default")
      (node (ref "DIGITAL1") (pin "2") (pinfunction "2_2") (pintype "passive"))
      (node (ref "IC4") (pin "25") (pinfunction "PC5_25") (pintype "bidirectional"))
    )
    (net (code "58") (name "/DIG2") (class "Default")
      (node (ref "DIGITAL1") (pin "3") (pinfunction "3_3") (pintype "passive"))
      (node (ref "IC4") (pin "28") (pinfunction "PB1_2_28") (pintype "bidirectional"))
      (node (ref "R14") (pin "1") (pinfunction "1_1") (pintype "passive"))
    )
    (net (code "59") (name "/DIG3") (class "Default")
      (node (ref "DIGITAL1") (pin "4") (pinfunction "4_4") (pintype "passive"))
      (node (ref "IC4") (pin "29") (pinfunction "PB10_29") (pintype "bidirectional"))
    )
    (net (code "60") (name "/DIG4") (class "Default")
      (node (ref "DIGITAL1") (pin "5") (pinfunction "5_5") (pintype "passive"))
      (node (ref "IC4") (pin "30") (pinfunction "PB11_30") (pintype "bidirectional"))
    )
    (net (code "61") (name "/DIG5") (class "Default")
      (node (ref "DIGITAL1") (pin "6") (pinfunction "6_6") (pintype "passive"))
      (node (ref "IC4") (pin "21") (pinfunction "PA5_21") (pintype "bidirectional"))
    )
    (net (code "62") (name "/DIG6") (class "Default")
      (node (ref "DIGITAL1") (pin "7") (pinfunction "7_7") (pintype "passive"))
      (node (ref "IC4") (pin "41") (pinfunction "PA8_41") (pintype "bidirectional"))
    )
    (net (code "63") (name "/DIG7") (class "Default")
      (node (ref "DIGITAL1") (pin "8") (pinfunction "8_8") (pintype "passive"))
      (node (ref "IC4") (pin "37") (pinfunction "PC6_37") (pintype "bidirectional"))
    )
    (net (code "64") (name "/DIG8") (class "Default")
      (node (ref "DIGITAL2") (pin "1") (pinfunction "1_1") (pintype "passive"))
      (node (ref "IC4") (pin "38") (pinfunction "PC7_38") (pintype "bidirectional"))
    )
    (net (code "65") (name "/DIG9") (class "Default")
      (node (ref "DIGITAL2") (pin "2") (pinfunction "2_2") (pintype "passive"))
      (node (ref "IC4") (pin "20") (pinfunction "PA4_20") (pintype "bidirectional"))
    )
    (net (code "66") (name "/DIG10") (class "Default")
      (node (ref "DIGITAL2") (pin "3") (pinfunction "3_3") (pintype "passive"))
      (node (ref "IC4") (pin "33") (pinfunction "PB12_33") (pintype "bidirectional"))
    )
    (net (code "67") (name "/DIG11") (class "Default")
      (node (ref "DIGITAL2") (pin "4") (pinfunction "4_4") (pintype "passive"))
      (node (ref "IC4") (pin "36") (pinfunction "PB15_36") (pintype "bidirectional"))
    )
    (net (code "68") (name "/DIG12") (class "Default")
      (node (ref "DIGITAL2") (pin "5") (pinfunction "5_5") (pintype "passive"))
      (node (ref "IC4") (pin "35") (pinfunction "PB14_35") (pintype "bidirectional"))
    )
    (net (code "69") (name "/DIG13") (class "Default")
      (node (ref "DIGITAL2") (pin "6") (pinfunction "6_6") (pintype "passive"))
      (node (ref "IC4") (pin "34") (pinfunction "PB13_34") (pintype "bidirectional"))
    )
    (net (code "70") (name "/DIG16") (class "Default")
      (node (ref "DIGITAL3") (pin "1") (pinfunction "1_1") (pintype "passive"))
      (node (ref "IC3") (pin "41") (pinfunction "IOB_63_41") (pintype "bidirectional"))
      (node (ref "IC4") (pin "54") (pinfunction "PD2_54") (pintype "bidirectional"))
      (node (ref "PMOD13") (pin "4") (pinfunction "4_4") (pintype "passive"))
      (node (ref "R7") (pin "1") (pinfunction "1_1") (pintype "passive"))
      (node (ref "S2") (pin "1") (pinfunction "1_1") (pintype "passive"))
      (node (ref "SD1") (pin "3") (pinfunction "CMD(DI)_3") (pintype "bidirectional"))
    )
    (net (code "71") (name "/DIG17") (class "Default")
      (node (ref "DIGITAL3") (pin "2") (pinfunction "2_2") (pintype "passive"))
      (node (ref "IC3") (pin "39") (pinfunction "IOB_61_39") (pintype "bidirectional"))
      (node (ref "IC4") (pin "51") (pinfunction "PC10_51") (pintype "bidirectional"))
      (node (ref "PMOD13") (pin "3") (pinfunction "3_3") (pintype "passive"))
      (node (ref "R8") (pin "1") (pinfunction "1_1") (pintype "passive"))
      (node (ref "S2") (pin "2") (pinfunction "2_2") (pintype "passive"))
      (node (ref "SD1") (pin "1") (pinfunction "DAT2_1") (pintype "bidirectional"))
    )
    (net (code "72") (name "/DIG18") (class "Default")
      (node (ref "DIGITAL3") (pin "3") (pinfunction "3_3") (pintype "passive"))
      (node (ref "IC3") (pin "38") (pinfunction "IOB_57_38") (pintype "bidirectional"))
      (node (ref "IC4") (pin "52") (pinfunction "PC11_52") (pintype "bidirectional"))
      (node (ref "PMOD13") (pin "2") (pinfunction "2_2") (pintype "passive"))
      (node (ref "R9") (pin "1") (pinfunction "1_1") (pintype "passive"))
      (node (ref "S1") (pin "1") (pinfunction "1_1") (pintype "passive"))
      (node (ref "SD1") (pin "2") (pinfunction "CD/DAT3(~{CS})_2") (pintype "bidirectional"))
    )
    (net (code "73") (name "/DIG19") (class "Default")
      (node (ref "DIGITAL3") (pin "4") (pinfunction "4_4") (pintype "passive"))
      (node (ref "IC3") (pin "37") (pinfunction "IOB_56_37") (pintype "bidirectional"))
      (node (ref "IC4") (pin "53") (pinfunction "PC12_53") (pintype "bidirectional"))
      (node (ref "PMOD13") (pin "1") (pinfunction "1_1") (pintype "passive"))
      (node (ref "R10") (pin "1") (pinfunction "1_1") (pintype "passive"))
      (node (ref "S1") (pin "2") (pinfunction "2_2") (pintype "passive"))
      (node (ref "SD1") (pin "5") (pinfunction "CLK(SCLK)_5") (pintype "input"))
    )
    (net (code "74") (name "/DONE") (class "Default")
      (node (ref "COMS") (pin "22") (pinfunction "22_22") (pintype "passive"))
      (node (ref "IC3") (pin "52") (pinfunction "IOB_82_GBIN4_52") (pintype "bidirectional"))
      (node (ref "IC3") (pin "65") (pinfunction "CDONE_65") (pintype "bidirectional"))
      (node (ref "IC4") (pin "59") (pinfunction "PB7_59") (pintype "power_in"))
      (node (ref "R26") (pin "1") (pinfunction "1_1") (pintype "passive"))
    )
    (net (code "75") (name "/EMISO") (class "Default")
      (node (ref "COMS") (pin "21") (pinfunction "21_21") (pintype "passive"))
      (node (ref "IC6") (pin "10") (pinfunction "3B2_10") (pintype "bidirectional"))
    )
    (net (code "76") (name "/EMOSI") (class "Default")
      (node (ref "COMS") (pin "19") (pinfunction "19_19") (pintype "passive"))
      (node (ref "IC6") (pin "6") (pinfunction "2B2_6") (pintype "bidirectional"))
    )
    (net (code "77") (name "/ESCK") (class "Default")
      (node (ref "COMS") (pin "23") (pinfunction "23_23") (pintype "passive"))
      (node (ref "IC6") (pin "3") (pinfunction "1B2_3") (pintype "bidirectional"))
    )
    (net (code "78") (name "/MISO") (class "Default")
      (node (ref "IC3") (pin "67") (pinfunction "IOB_105_SDO_67") (pintype "bidirectional"))
      (node (ref "IC4") (pin "56") (pinfunction "PB4_56") (pintype "bidirectional"))
      (node (ref "IC6") (pin "9") (pinfunction "3A_9") (pintype "bidirectional"))
    )
    (net (code "79") (name "/MOSI") (class "Default")
      (node (ref "IC3") (pin "68") (pinfunction "IOB_106_SDI_68") (pintype "bidirectional"))
      (node (ref "IC4") (pin "57") (pinfunction "PB5_57") (pintype "bidirectional"))
      (node (ref "IC6") (pin "7") (pinfunction "2A_7") (pintype "bidirectional"))
    )
    (net (code "80") (name "/OE") (class "Default")
      (node (ref "COMS") (pin "15") (pinfunction "15_15") (pintype "passive"))
      (node (ref "IC4") (pin "4") (pinfunction "PC15-OSC32_OUT_4") (pintype "output"))
      (node (ref "IC6") (pin "15") (pinfunction "~{OE}_15") (pintype "bidirectional"))
    )
    (net (code "81") (name "/P0") (class "Default")
      (node (ref "IC1") (pin "9") (pinfunction "CTS_9") (pintype "bidirectional"))
      (node (ref "IC3") (pin "94") (pinfunction "IOR_141_GBIN2_94") (pintype "bidirectional"))
      (node (ref "PMOD1/2") (pin "11") (pinfunction "11_11") (pintype "passive"))
    )
    (net (code "82") (name "/P1") (class "Default")
      (node (ref "IC1") (pin "14") (pinfunction "RTS_14") (pintype "bidirectional"))
      (node (ref "IC3") (pin "128") (pinfunction "IOT_197_GBIN1_128") (pintype "bidirectional"))
      (node (ref "IC3") (pin "91") (pinfunction "IOR_139_91") (pintype "bidirectional"))
      (node (ref "PMOD1/2") (pin "9") (pinfunction "9_9") (pintype "passive"))
    )
    (net (code "83") (name "/P2") (class "Default")
      (node (ref "IC3") (pin "88") (pinfunction "IOR_137_88") (pintype "bidirectional"))
      (node (ref "PMOD1/2") (pin "7") (pinfunction "7_7") (pintype "passive"))
      (node (ref "R27") (pin "2") (pinfunction "2_2") (pintype "passive"))
    )
    (net (code "84") (name "/P3") (class "Default")
      (node (ref "IC3") (pin "85") (pinfunction "IOR_128_85") (pintype "bidirectional"))
      (node (ref "PMOD1/2") (pin "5") (pinfunction "5_5") (pintype "passive"))
      (node (ref "R25") (pin "2") (pinfunction "2_2") (pintype "passive"))
    )
    (net (code "85") (name "/P4") (class "Default")
      (node (ref "IC3") (pin "95") (pinfunction "IOR_144_95") (pintype "bidirectional"))
      (node (ref "PMOD1/2") (pin "12") (pinfunction "12_12") (pintype "passive"))
    )
    (net (code "86") (name "/P5") (class "Default")
      (node (ref "IC3") (pin "93") (pinfunction "IOR_140_GBIN3_93") (pintype "bidirectional"))
      (node (ref "PMOD1/2") (pin "10") (pinfunction "10_10") (pintype "passive"))
    )
    (net (code "87") (name "/P6") (class "Default")
      (node (ref "IC3") (pin "90") (pinfunction "IOR_138_90") (pintype "bidirectional"))
      (node (ref "PMOD1/2") (pin "8") (pinfunction "8_8") (pintype "passive"))
    )
    (net (code "88") (name "/P7") (class "Default")
      (node (ref "IC3") (pin "87") (pinfunction "IOR_136_87") (pintype "bidirectional"))
      (node (ref "PMOD1/2") (pin "6") (pinfunction "6_6") (pintype "passive"))
    )
    (net (code "89") (name "/P8") (class "Default")
      (node (ref "IC3") (pin "105") (pinfunction "IOR_165_105") (pintype "bidirectional"))
      (node (ref "PMOD3/4") (pin "11") (pinfunction "11_11") (pintype "passive"))
    )
    (net (code "90") (name "/P9") (class "Default")
      (node (ref "IC3") (pin "102") (pinfunction "IOR_161_102") (pintype "bidirectional"))
      (node (ref "PMOD3/4") (pin "9") (pinfunction "9_9") (pintype "passive"))
    )
    (net (code "91") (name "/P10") (class "Default")
      (node (ref "IC3") (pin "99") (pinfunction "IOR_152_99") (pintype "bidirectional"))
      (node (ref "PMOD3/4") (pin "7") (pinfunction "7_7") (pintype "passive"))
    )
    (net (code "92") (name "/P11") (class "Default")
      (node (ref "IC3") (pin "97") (pinfunction "IOR_147_97") (pintype "bidirectional"))
      (node (ref "PMOD3/4") (pin "5") (pinfunction "5_5") (pintype "passive"))
    )
    (net (code "93") (name "/P12") (class "Default")
      (node (ref "IC3") (pin "104") (pinfunction "IOR_164_104") (pintype "bidirectional"))
      (node (ref "PMOD3/4") (pin "12") (pinfunction "12_12") (pintype "passive"))
    )
    (net (code "94") (name "/P13") (class "Default")
      (node (ref "IC3") (pin "101") (pinfunction "IOR_160_101") (pintype "bidirectional"))
      (node (ref "PMOD3/4") (pin "10") (pinfunction "10_10") (pintype "passive"))
    )
    (net (code "95") (name "/P14") (class "Default")
      (node (ref "IC3") (pin "98") (pinfunction "IOR_148_98") (pintype "bidirectional"))
      (node (ref "PMOD3/4") (pin "8") (pinfunction "8_8") (pintype "passive"))
    )
    (net (code "96") (name "/P15") (class "Default")
      (node (ref "IC3") (pin "96") (pinfunction "IOR_146_96") (pintype "bidirectional"))
      (node (ref "PMOD3/4") (pin "6") (pinfunction "6_6") (pintype "passive"))
    )
    (net (code "97") (name "/P16") (class "Default")
      (node (ref "IC3") (pin "143") (pinfunction "IOT_221_143") (pintype "bidirectional"))
      (node (ref "PMOD5/6") (pin "11") (pinfunction "11_11") (pintype "passive"))
    )
    (net (code "98") (name "/P17") (class "Default")
      (node (ref "IC3") (pin "114") (pinfunction "IOT_171_114") (pintype "bidirectional"))
      (node (ref "PMOD5/6") (pin "9") (pinfunction "9_9") (pintype "passive"))
    )
    (net (code "99") (name "/P18") (class "Default")
      (node (ref "IC3") (pin "112") (pinfunction "IOT_169_112") (pintype "bidirectional"))
      (node (ref "PMOD5/6") (pin "7") (pinfunction "7_7") (pintype "passive"))
    )
    (net (code "100") (name "/P19") (class "Default")
      (node (ref "IC3") (pin "107") (pinfunction "IOR_167_107") (pintype "bidirectional"))
      (node (ref "PMOD5/6") (pin "5") (pinfunction "5_5") (pintype "passive"))
    )
    (net (code "101") (name "/P20") (class "Default")
      (node (ref "IC3") (pin "144") (pinfunction "IOT_222_144") (pintype "bidirectional"))
      (node (ref "PMOD5/6") (pin "12") (pinfunction "12_12") (pintype "passive"))
    )
    (net (code "102") (name "/P21") (class "Default")
      (node (ref "IC3") (pin "113") (pinfunction "IOT_170_113") (pintype "bidirectional"))
      (node (ref "PMOD5/6") (pin "10") (pinfunction "10_10") (pintype "passive"))
    )
    (net (code "103") (name "/P22") (class "Default")
      (node (ref "IC3") (pin "110") (pinfunction "IOT_168_110") (pintype "bidirectional"))
      (node (ref "PMOD5/6") (pin "8") (pinfunction "8_8") (pintype "passive"))
    )
    (net (code "104") (name "/P23") (class "Default")
      (node (ref "IC3") (pin "106") (pinfunction "IOR_166_106") (pintype "bidirectional"))
      (node (ref "PMOD5/6") (pin "6") (pinfunction "6_6") (pintype "passive"))
    )
    (net (code "105") (name "/P24") (class "Default")
      (node (ref "IC3") (pin "10") (pinfunction "IOL_5B_10") (pintype "bidirectional"))
      (node (ref "OLI-EXP") (pin "15") (pinfunction "KL_15") (pintype "passive"))
      (node (ref "PMOD7/8") (pin "11") (pinfunction "11_11") (pintype "passive"))
    )
    (net (code "106") (name "/P25") (class "Default")
      (node (ref "IC3") (pin "9") (pinfunction "IOL_5A_9") (pintype "bidirectional"))
      (node (ref "OLI-EXP") (pin "13") (pinfunction "KL_13") (pintype "passive"))
      (node (ref "PMOD7/8") (pin "9") (pinfunction "9_9") (pintype "passive"))
    )
    (net (code "107") (name "/P26") (class "Default")
      (node (ref "IC3") (pin "2") (pinfunction "IOL_2B_2") (pintype "bidirectional"))
      (node (ref "OLI-EXP") (pin "7") (pinfunction "KL_7") (pintype "passive"))
      (node (ref "PMOD7/8") (pin "7") (pinfunction "7_7") (pintype "passive"))
    )
    (net (code "108") (name "/P27") (class "Default")
      (node (ref "IC3") (pin "1") (pinfunction "IOL_2A_1") (pintype "bidirectional"))
      (node (ref "OLI-EXP") (pin "5") (pinfunction "KL_5") (pintype "passive"))
      (node (ref "PMOD7/8") (pin "5") (pinfunction "5_5") (pintype "passive"))
    )
    (net (code "109") (name "/P28") (class "Default")
      (node (ref "IC3") (pin "8") (pinfunction "IOL_4B_8") (pintype "bidirectional"))
      (node (ref "OLI-EXP") (pin "12") (pinfunction "KL_12") (pintype "passive"))
      (node (ref "PMOD7/8") (pin "12") (pinfunction "12_12") (pintype "passive"))
    )
    (net (code "110") (name "/P29") (class "Default")
      (node (ref "IC3") (pin "7") (pinfunction "IOL_4A_7") (pintype "bidirectional"))
      (node (ref "OLI-EXP") (pin "10") (pinfunction "KL_10") (pintype "passive"))
      (node (ref "PMOD7/8") (pin "10") (pinfunction "10_10") (pintype "passive"))
    )
    (net (code "111") (name "/P30") (class "Default")
      (node (ref "IC3") (pin "4") (pinfunction "IOL_3B_4") (pintype "bidirectional"))
      (node (ref "OLI-EXP") (pin "11") (pinfunction "KL_11") (pintype "passive"))
      (node (ref "PMOD7/8") (pin "8") (pinfunction "8_8") (pintype "passive"))
    )
    (net (code "112") (name "/P31") (class "Default")
      (node (ref "IC3") (pin "3") (pinfunction "IOL_3A_3") (pintype "bidirectional"))
      (node (ref "OLI-EXP") (pin "9") (pinfunction "KL_9") (pintype "passive"))
      (node (ref "PMOD7/8") (pin "6") (pinfunction "6_6") (pintype "passive"))
    )
    (net (code "113") (name "/P32") (class "Default")
      (node (ref "IC3") (pin "20") (pinfunction "IOL_13B_GBIN7_20") (pintype "bidirectional"))
      (node (ref "OLI-EXP") (pin "23") (pinfunction "KL_23") (pintype "passive"))
      (node (ref "PMOD9/10") (pin "11") (pinfunction "11_11") (pintype "passive"))
    )
    (net (code "114") (name "/P33") (class "Default")
      (node (ref "IC3") (pin "19") (pinfunction "IOL_13A_19") (pintype "bidirectional"))
      (node (ref "OLI-EXP") (pin "21") (pinfunction "KL_21") (pintype "passive"))
      (node (ref "PMOD9/10") (pin "9") (pinfunction "9_9") (pintype "passive"))
    )
    (net (code "115") (name "/P34") (class "Default")
      (node (ref "IC3") (pin "16") (pinfunction "IOL_10B_16") (pintype "bidirectional"))
      (node (ref "OLI-EXP") (pin "19") (pinfunction "KL_19") (pintype "passive"))
      (node (ref "PMOD9/10") (pin "7") (pinfunction "7_7") (pintype "passive"))
    )
    (net (code "116") (name "/P35") (class "Default")
      (node (ref "IC3") (pin "15") (pinfunction "IOL_10A_15") (pintype "bidirectional"))
      (node (ref "OLI-EXP") (pin "17") (pinfunction "KL_17") (pintype "passive"))
      (node (ref "PMOD9/10") (pin "5") (pinfunction "5_5") (pintype "passive"))
    )
    (net (code "117") (name "/P36") (class "Default")
      (node (ref "IC3") (pin "18") (pinfunction "IOL_12B_18") (pintype "bidirectional"))
      (node (ref "OLI-EXP") (pin "20") (pinfunction "KL_20") (pintype "passive"))
      (node (ref "PMOD9/10") (pin "12") (pinfunction "12_12") (pintype "passive"))
    )
    (net (code "118") (name "/P37") (class "Default")
      (node (ref "IC3") (pin "17") (pinfunction "IOL_12A_17") (pintype "bidirectional"))
      (node (ref "OLI-EXP") (pin "18") (pinfunction "KL_18") (pintype "passive"))
      (node (ref "PMOD9/10") (pin "10") (pinfunction "10_10") (pintype "passive"))
    )
    (net (code "119") (name "/P38") (class "Default")
      (node (ref "IC3") (pin "12") (pinfunction "IOL_8B_12") (pintype "bidirectional"))
      (node (ref "OLI-EXP") (pin "16") (pinfunction "KL_16") (pintype "passive"))
      (node (ref "PMOD9/10") (pin "8") (pinfunction "8_8") (pintype "passive"))
    )
    (net (code "120") (name "/P39") (class "Default")
      (node (ref "IC3") (pin "11") (pinfunction "IOL_8A_11") (pintype "bidirectional"))
      (node (ref "OLI-EXP") (pin "14") (pinfunction "KL_14") (pintype "passive"))
      (node (ref "PMOD9/10") (pin "6") (pinfunction "6_6") (pintype "passive"))
    )
    (net (code "121") (name "/P40") (class "Default")
      (node (ref "IC3") (pin "34") (pinfunction "IOL_25B_34") (pintype "bidirectional"))
      (node (ref "OLI-EXP") (pin "34") (pinfunction "KL_34") (pintype "passive"))
      (node (ref "PMOD11/12") (pin "11") (pinfunction "11_11") (pintype "passive"))
    )
    (net (code "122") (name "/P41") (class "Default")
      (node (ref "IC3") (pin "33") (pinfunction "IOL_25A_33") (pintype "bidirectional"))
      (node (ref "OLI-EXP") (pin "32") (pinfunction "KL_32") (pintype "passive"))
      (node (ref "PMOD11/12") (pin "9") (pinfunction "9_9") (pintype "passive"))
    )
    (net (code "123") (name "/P42") (class "Default")
      (node (ref "IC3") (pin "22") (pinfunction "IOL_14B_22") (pintype "bidirectional"))
      (node (ref "OLI-EXP") (pin "25") (pinfunction "KL_25") (pintype "passive"))
      (node (ref "PMOD11/12") (pin "7") (pinfunction "7_7") (pintype "passive"))
    )
    (net (code "124") (name "/P43") (class "Default")
      (node (ref "IC3") (pin "21") (pinfunction "IOL_14A_GBIN6_21") (pintype "bidirectional"))
      (node (ref "OLI-EXP") (pin "22") (pinfunction "KL_22") (pintype "passive"))
      (node (ref "PMOD11/12") (pin "5") (pinfunction "5_5") (pintype "passive"))
    )
    (net (code "125") (name "/P44") (class "Default")
      (node (ref "IC3") (pin "32") (pinfunction "IOL_24B_32") (pintype "bidirectional"))
      (node (ref "OLI-EXP") (pin "30") (pinfunction "KL_30") (pintype "passive"))
      (node (ref "PMOD11/12") (pin "12") (pinfunction "12_12") (pintype "passive"))
    )
    (net (code "126") (name "/P45") (class "Default")
      (node (ref "IC3") (pin "31") (pinfunction "IOL_24A_31") (pintype "bidirectional"))
      (node (ref "OLI-EXP") (pin "28") (pinfunction "KL_28") (pintype "passive"))
      (node (ref "PMOD11/12") (pin "10") (pinfunction "10_10") (pintype "passive"))
    )
    (net (code "127") (name "/P46") (class "Default")
      (node (ref "IC3") (pin "26") (pinfunction "IOL_18B_26") (pintype "bidirectional"))
      (node (ref "OLI-EXP") (pin "26") (pinfunction "KL_26") (pintype "passive"))
      (node (ref "PMOD11/12") (pin "8") (pinfunction "8_8") (pintype "passive"))
    )
    (net (code "128") (name "/P47") (class "Default")
      (node (ref "IC3") (pin "25") (pinfunction "IOL_18_A_25") (pintype "bidirectional"))
      (node (ref "OLI-EXP") (pin "24") (pinfunction "KL_24") (pintype "passive"))
      (node (ref "PMOD11/12") (pin "6") (pinfunction "6_6") (pintype "passive"))
    )
    (net (code "129") (name "/P52") (class "Default")
      (node (ref "IC6") (pin "14") (pinfunction "4B1_14") (pintype "bidirectional"))
      (node (ref "PMOD14") (pin "1") (pinfunction "1_1") (pintype "passive"))
      (node (ref "R1") (pin "2") (pinfunction "2_2") (pintype "passive"))
    )
    (net (code "130") (name "/P53") (class "Default")
      (node (ref "IC6") (pin "11") (pinfunction "3B1_11") (pintype "bidirectional"))
      (node (ref "PMOD14") (pin "2") (pinfunction "2_2") (pintype "passive"))
      (node (ref "R3") (pin "2") (pinfunction "2_2") (pintype "passive"))
    )
    (net (code "131") (name "/P54") (class "Default")
      (node (ref "IC6") (pin "5") (pinfunction "2B1_5") (pintype "bidirectional"))
      (node (ref "PMOD14") (pin "3") (pinfunction "3_3") (pintype "passive"))
      (node (ref "R2") (pin "2") (pinfunction "2_2") (pintype "passive"))
    )
    (net (code "132") (name "/P55") (class "Default")
      (node (ref "IC6") (pin "2") (pinfunction "1B1_2") (pintype "bidirectional"))
      (node (ref "PMOD14") (pin "4") (pinfunction "4_4") (pintype "passive"))
      (node (ref "R4") (pin "2") (pinfunction "2_2") (pintype "passive"))
    )
    (net (code "133") (name "/QCK") (class "Default")
      (node (ref "IC3") (pin "82") (pinfunction "IOR_118_82") (pintype "bidirectional"))
      (node (ref "IC4") (pin "17") (pinfunction "PA3_17") (pintype "bidirectional"))
    )
    (net (code "134") (name "/QD0") (class "Default")
      (node (ref "IC3") (pin "83") (pinfunction "IOR_119_83") (pintype "bidirectional"))
      (node (ref "IC4") (pin "27") (pinfunction "PB1_27") (pintype "bidirectional"))
    )
    (net (code "135") (name "/QD1") (class "Default")
      (node (ref "IC3") (pin "84") (pinfunction "IOR_120_84") (pintype "bidirectional"))
      (node (ref "IC4") (pin "26") (pinfunction "PB0_26") (pintype "bidirectional"))
    )
    (net (code "136") (name "/QD2") (class "Default")
      (node (ref "IC3") (pin "79") (pinfunction "IOR_115_79") (pintype "bidirectional"))
      (node (ref "IC4") (pin "23") (pinfunction "PA7_23") (pintype "power_in"))
    )
    (net (code "137") (name "/QD3") (class "Default")
      (node (ref "IC3") (pin "80") (pinfunction "IOR_116_80") (pintype "bidirectional"))
      (node (ref "IC4") (pin "22") (pinfunction "PA6_22") (pintype "bidirectional"))
    )
    (net (code "138") (name "/RAM_CS") (class "Default")
      (node (ref "IC2") (pin "6") (pinfunction "~{CS1}_6") (pintype "input"))
      (node (ref "IC3") (pin "23") (pinfunction "IOL_17A_23") (pintype "bidirectional"))
      (node (ref "OLI-EXP") (pin "27") (pinfunction "KL_27") (pintype "passive"))
      (node (ref "R30") (pin "1") (pinfunction "1_1") (pintype "passive"))
    )
    (net (code "139") (name "/RAM_LB") (class "Default")
      (node (ref "IC2") (pin "39") (pinfunction "~{LB}_39") (pintype "passive"))
      (node (ref "IC3") (pin "24") (pinfunction "IOL_17B_24") (pintype "bidirectional"))
      (node (ref "OLI-EXP") (pin "29") (pinfunction "KL_29") (pintype "passive"))
    )
    (net (code "140") (name "/RAM_OE") (class "Default")
      (node (ref "IC2") (pin "41") (pinfunction "~{OE}_41") (pintype "input"))
      (node (ref "IC3") (pin "29") (pinfunction "IOL_23B_29") (pintype "bidirectional"))
      (node (ref "OLI-EXP") (pin "33") (pinfunction "KL_33") (pintype "passive"))
    )
    (net (code "141") (name "/RAM_UB") (class "Default")
      (node (ref "IC2") (pin "40") (pinfunction "~{UB}_40") (pintype "passive"))
      (node (ref "IC3") (pin "28") (pinfunction "IOL_23A_28") (pintype "bidirectional"))
      (node (ref "OLI-EXP") (pin "31") (pinfunction "KL_31") (pintype "passive"))
    )
    (net (code "142") (name "/RAM_WE") (class "Default")
      (node (ref "IC2") (pin "17") (pinfunction "~{WE}_17") (pintype "input"))
      (node (ref "IC3") (pin "120") (pinfunction "IOT_179_120") (pintype "bidirectional"))
    )
    (net (code "143") (name "/RESET") (class "Default")
      (node (ref "COMS") (pin "18") (pinfunction "18_18") (pintype "passive"))
      (node (ref "IC3") (pin "66") (pinfunction "CRESET_B_66") (pintype "bidirectional"))
      (node (ref "IC4") (pin "58") (pinfunction "PB6_58") (pintype "bidirectional"))
    )
    (net (code "144") (name "/RX") (class "Default")
      (node (ref "COMS") (pin "8") (pinfunction "8_8") (pintype "passive"))
      (node (ref "IC1") (pin "2") (pinfunction "TX_2") (pintype "bidirectional"))
      (node (ref "IC4") (pin "43") (pinfunction "PA10_43") (pintype "bidirectional"))
      (node (ref "R27") (pin "1") (pinfunction "1_1") (pintype "passive"))
    )
    (net (code "145") (name "/S") (class "Default")
      (node (ref "COMS") (pin "12") (pinfunction "12_12") (pintype "passive"))
      (node (ref "IC4") (pin "3") (pinfunction "PC14-OSC32_IN_3") (pintype "input"))
      (node (ref "IC6") (pin "1") (pinfunction "B2/~{B1}_1") (pintype "bidirectional"))
    )
    (net (code "146") (name "/SCK") (class "Default")
      (node (ref "IC3") (pin "70") (pinfunction "IOB_107_SCK_70") (pintype "bidirectional"))
      (node (ref "IC4") (pin "55") (pinfunction "PB3_55") (pintype "bidirectional"))
      (node (ref "IC6") (pin "4") (pinfunction "1A_4") (pintype "bidirectional"))
    )
    (net (code "147") (name "/SCL") (class "Default")
      (node (ref "COMS") (pin "5") (pinfunction "5_5") (pintype "passive"))
      (node (ref "DIGITAL2") (pin "10") (pinfunction "10_10") (pintype "passive"))
      (node (ref "IC4") (pin "61") (pinfunction "PB8_61") (pintype "bidirectional"))
    )
    (net (code "148") (name "/SDA") (class "Default")
      (node (ref "COMS") (pin "3") (pinfunction "3_3") (pintype "passive"))
      (node (ref "DIGITAL2") (pin "9") (pinfunction "9_9") (pintype "passive"))
      (node (ref "IC4") (pin "62") (pinfunction "PB9_62") (pintype "bidirectional"))
    )
    (net (code "149") (name "/SWCLK") (class "Default")
      (node (ref "COMS") (pin "7") (pinfunction "7_7") (pintype "passive"))
      (node (ref "IC4") (pin "49") (pinfunction "PA14_49") (pintype "bidirectional"))
      (node (ref "R13") (pin "2") (pinfunction "2_2") (pintype "passive"))
    )
    (net (code "150") (name "/SWDIO") (class "Default")
      (node (ref "COMS") (pin "11") (pinfunction "11_11") (pintype "passive"))
      (node (ref "IC4") (pin "46") (pinfunction "PA13_46") (pintype "bidirectional"))
      (node (ref "R11") (pin "2") (pinfunction "2_2") (pintype "passive"))
    )
    (net (code "151") (name "/TX") (class "Default")
      (node (ref "COMS") (pin "10") (pinfunction "10_10") (pintype "passive"))
      (node (ref "IC1") (pin "3") (pinfunction "RX_3") (pintype "bidirectional"))
      (node (ref "IC4") (pin "42") (pinfunction "PA9_42") (pintype "bidirectional"))
      (node (ref "R25") (pin "1") (pinfunction "1_1") (pintype "passive"))
    )
    (net (code "152") (name "/VBAT") (class "Default")
      (node (ref "C33") (pin "2") (pinfunction "2_2") (pintype "passive"))
      (node (ref "IC4") (pin "1") (pinfunction "VBAT_1") (pintype "input"))
    )
    (net (code "153") (name "/VBUS") (class "Default")
      (node (ref "COM") (pin "P$1") (pinfunction "VBUS_P$1") (pintype "bidirectional"))
      (node (ref "D1") (pin "A") (pinfunction "A_A") (pintype "passive"))
      (node (ref "U$2") (pin "P$1") (pinfunction "VBUS_P$1") (pintype "bidirectional"))
    )
    (net (code "154") (name "/VDD_ADC") (class "Default")
      (node (ref "C28") (pin "2") (pinfunction "2_2") (pintype "passive"))
      (node (ref "IC4") (pin "13") (pinfunction "VDDA_13") (pintype "power_in"))
      (node (ref "L3") (pin "2") (pinfunction "2_2") (pintype "passive"))
    )
    (net (code "155") (name "/~{ESS}") (class "Default")
      (node (ref "COMS") (pin "24") (pinfunction "24_24") (pintype "passive"))
      (node (ref "IC6") (pin "13") (pinfunction "4B2_13") (pintype "bidirectional"))
    )
    (net (code "156") (name "/~{QCS}") (class "Default")
      (node (ref "IC3") (pin "81") (pinfunction "IOR_117_81") (pintype "bidirectional"))
      (node (ref "IC4") (pin "16") (pinfunction "PA2_16") (pintype "bidirectional"))
    )
    (net (code "157") (name "/~{RESET}") (class "Default")
      (node (ref "C1") (pin "1") (pinfunction "1_1") (pintype "passive"))
      (node (ref "COMS") (pin "13") (pinfunction "13_13") (pintype "passive"))
      (node (ref "DIGITAL3") (pin "7") (pinfunction "7_7") (pintype "passive"))
      (node (ref "IC4") (pin "7") (pinfunction "NRST_7") (pintype "output"))
      (node (ref "R23") (pin "1") (pinfunction "1_1") (pintype "passive"))
      (node (ref "S0") (pin "2") (pinfunction "2_2") (pintype "passive"))
    )
    (net (code "158") (name "/~{SS}") (class "Default")
      (node (ref "IC3") (pin "71") (pinfunction "IOB_108_SS_71") (pintype "bidirectional"))
      (node (ref "IC4") (pin "50") (pinfunction "PA15_50") (pintype "bidirectional"))
      (node (ref "IC6") (pin "12") (pinfunction "4A_12") (pintype "bidirectional"))
      (node (ref "R35") (pin "2") (pinfunction "2_2") (pintype "passive"))
    )
    (net (code "159") (name "5V") (class "Default")
      (node (ref "5V") (pin "TP") (pinfunction "TP_TP") (pintype "input"))
      (node (ref "C16") (pin "1") (pinfunction "1_1") (pintype "passive"))
      (node (ref "C17") (pin "1") (pinfunction "1_1") (pintype "passive"))
      (node (ref "C20") (pin "1") (pinfunction "1_1") (pintype "passive"))
      (node (ref "C53") (pin "1") (pinfunction "1_1") (pintype "passive"))
      (node (ref "C60") (pin "1") (pinfunction "1_1") (pintype "passive"))
      (node (ref "DIGITAL3") (pin "12") (pinfunction "12_12") (pintype "passive"))
      (node (ref "DIGITAL3") (pin "9") (pinfunction "9_9") (pintype "passive"))
      (node (ref "F1") (pin "2") (pinfunction "2_2") (pintype "passive"))
      (node (ref "IC8") (pin "3") (pinfunction "VIN_3") (pintype "input"))
      (node (ref "OLI-EXP") (pin "1") (pinfunction "KL_1") (pintype "passive"))
    )
    (net (code "160") (name "GND") (class "Default")
      (node (ref "C1") (pin "2") (pinfunction "2_2") (pintype "passive"))
      (node (ref "C10") (pin "1") (pinfunction "1_1") (pintype "passive"))
      (node (ref "C11") (pin "2") (pinfunction "2_2") (pintype "passive"))
      (node (ref "C12") (pin "2") (pinfunction "2_2") (pintype "passive"))
      (node (ref "C13") (pin "2") (pinfunction "2_2") (pintype "passive"))
      (node (ref "C14") (pin "2") (pinfunction "2_2") (pintype "passive"))
      (node (ref "C16") (pin "2") (pinfunction "2_2") (pintype "passive"))
      (node (ref "C17") (pin "2") (pinfunction "2_2") (pintype "passive"))
      (node (ref "C18") (pin "2") (pinfunction "2_2") (pintype "passive"))
      (node (ref "C19") (pin "2") (pinfunction "2_2") (pintype "passive"))
      (node (ref "C2") (pin "2") (pinfunction "2_2") (pintype "passive"))
      (node (ref "C20") (pin "2") (pinfunction "2_2") (pintype "passive"))
      (node (ref "C23") (pin "2") (pinfunction "2_2") (pintype "passive"))
      (node (ref "C24") (pin "1") (pinfunction "1_1") (pintype "passive"))
      (node (ref "C25") (pin "1") (pinfunction "1_1") (pintype "passive"))
      (node (ref "C26") (pin "1") (pinfunction "1_1") (pintype "passive"))
      (node (ref "C27") (pin "1") (pinfunction "1_1") (pintype "passive"))
      (node (ref "C28") (pin "1") (pinfunction "1_1") (pintype "passive"))
      (node (ref "C29") (pin "1") (pinfunction "1_1") (pintype "passive"))
      (node (ref "C3") (pin "2") (pinfunction "2_2") (pintype "passive"))
      (node (ref "C30") (pin "1") (pinfunction "1_1") (pintype "passive"))
      (node (ref "C31") (pin "1") (pinfunction "1_1") (pintype "passive"))
      (node (ref "C32") (pin "1") (pinfunction "1_1") (pintype "passive"))
      (node (ref "C33") (pin "1") (pinfunction "1_1") (pintype "passive"))
      (node (ref "C34") (pin "1") (pinfunction "1_1") (pintype "passive"))
      (node (ref "C35") (pin "2") (pinfunction "2_2") (pintype "passive"))
      (node (ref "C37") (pin "2") (pinfunction "2_2") (pintype "passive"))
      (node (ref "C38") (pin "2") (pinfunction "2_2") (pintype "passive"))
      (node (ref "C39") (pin "1") (pinfunction "1_1") (pintype "passive"))
      (node (ref "C4") (pin "2") (pinfunction "2_2") (pintype "passive"))
      (node (ref "C40") (pin "1") (pinfunction "1_1") (pintype "passive"))
      (node (ref "C41") (pin "1") (pinfunction "1_1") (pintype "passive"))
      (node (ref "C42") (pin "2") (pinfunction "2_2") (pintype "passive"))
      (node (ref "C43") (pin "2") (pinfunction "2_2") (pintype "passive"))
      (node (ref "C44") (pin "2") (pinfunction "2_2") (pintype "passive"))
      (node (ref "C45") (pin "2") (pinfunction "2_2") (pintype "passive"))
      (node (ref "C46") (pin "2") (pinfunction "2_2") (pintype "passive"))
      (node (ref "C47") (pin "2") (pinfunction "2_2") (pintype "passive"))
      (node (ref "C48") (pin "2") (pinfunction "2_2") (pintype "passive"))
      (node (ref "C49") (pin "2") (pinfunction "2_2") (pintype "passive"))
      (node (ref "C5") (pin "2") (pinfunction "2_2") (pintype "passive"))
      (node (ref "C50") (pin "2") (pinfunction "2_2") (pintype "passive"))
      (node (ref "C51") (pin "2") (pinfunction "2_2") (pintype "passive"))
      (node (ref "C52") (pin "2") (pinfunction "2_2") (pintype "passive"))
      (node (ref "C53") (pin "2") (pinfunction "2_2") (pintype "passive"))
      (node (ref "C54") (pin "2") (pinfunction "2_2") (pintype "passive"))
      (node (ref "C55") (pin "2") (pinfunction "2_2") (pintype "passive"))
      (node (ref "C56") (pin "2") (pinfunction "2_2") (pintype "passive"))
      (node (ref "C57") (pin "2") (pinfunction "2_2") (pintype "passive"))
      (node (ref "C58") (pin "1") (pinfunction "1_1") (pintype "passive"))
      (node (ref "C59") (pin "2") (pinfunction "2_2") (pintype "passive"))
      (node (ref "C6") (pin "1") (pinfunction "1_1") (pintype "passive"))
      (node (ref "C60") (pin "2") (pinfunction "2_2") (pintype "passive"))
      (node (ref "C61") (pin "-") (pinfunction "-_-") (pintype "passive"))
      (node (ref "C62") (pin "1") (pinfunction "1_1") (pintype "passive"))
      (node (ref "C63") (pin "1") (pinfunction "1_1") (pintype "passive"))
      (node (ref "C7") (pin "2") (pinfunction "2_2") (pintype "passive"))
      (node (ref "C8") (pin "2") (pinfunction "2_2") (pintype "passive"))
      (node (ref "COM") (pin "P$5") (pinfunction "GND_P$5") (pintype "bidirectional"))
      (node (ref "COMS") (pin "14") (pinfunction "14_14") (pintype "passive"))
      (node (ref "COMS") (pin "20") (pinfunction "20_20") (pintype "passive"))
      (node (ref "COMS") (pin "25") (pinfunction "25_25") (pintype "passive"))
      (node (ref "COMS") (pin "6") (pinfunction "6_6") (pintype "passive"))
      (node (ref "COMS") (pin "9") (pinfunction "9_9") (pintype "passive"))
      (node (ref "DIGITAL2") (pin "7") (pinfunction "7_7") (pintype "passive"))
      (node (ref "DIGITAL3") (pin "10") (pinfunction "10_10") (pintype "passive"))
      (node (ref "DIGITAL3") (pin "11") (pinfunction "11_11") (pintype "passive"))
      (node (ref "ESD1") (pin "1") (pinfunction "GND_1") (pintype "bidirectional"))
      (node (ref "IC1") (pin "1") (pinfunction "GND_1") (pintype "bidirectional"))
      (node (ref "IC2") (pin "12") (pinfunction "GND_2_12") (pintype "passive"))
      (node (ref "IC2") (pin "34") (pinfunction "GND_34") (pintype "passive"))
      (node (ref "IC3") (pin "103") (pinfunction "GND_103") (pintype "bidirectional"))
      (node (ref "IC3") (pin "13") (pinfunction "GND_13") (pintype "bidirectional"))
      (node (ref "IC3") (pin "132") (pinfunction "GND_132") (pintype "bidirectional"))
      (node (ref "IC3") (pin "14") (pinfunction "GND_14") (pintype "bidirectional"))
      (node (ref "IC3") (pin "140") (pinfunction "GND_140") (pintype "bidirectional"))
      (node (ref "IC3") (pin "5") (pinfunction "GND_5") (pintype "bidirectional"))
      (node (ref "IC3") (pin "59") (pinfunction "GND_59") (pintype "bidirectional"))
      (node (ref "IC3") (pin "69") (pinfunction "GND_69") (pintype "bidirectional"))
      (node (ref "IC3") (pin "86") (pinfunction "GND_86") (pintype "bidirectional"))
      (node (ref "IC4") (pin "12") (pinfunction "VSSA_12") (pintype "passive"))
      (node (ref "IC4") (pin "18") (pinfunction "VSS_4_18") (pintype "passive"))
      (node (ref "IC4") (pin "31") (pinfunction "VSS_1_31") (pintype "passive"))
      (node (ref "IC4") (pin "47") (pinfunction "VSS_2_47") (pintype "passive"))
      (node (ref "IC4") (pin "63") (pinfunction "VSS_3_63") (pintype "passive"))
      (node (ref "IC6") (pin "8") (pinfunction "GND_8") (pintype "power_in"))
      (node (ref "IC7") (pin "2") (pinfunction "GND_2") (pintype "power_in"))
      (node (ref "IC8") (pin "1") (pinfunction "GND_1") (pintype "power_in"))
      (node (ref "LED1") (pin "C") (pinfunction "C_C") (pintype "passive"))
      (node (ref "LED2") (pin "C") (pinfunction "C_C") (pintype "passive"))
      (node (ref "LED3") (pin "C") (pinfunction "C_C") (pintype "passive"))
      (node (ref "LED4") (pin "C") (pinfunction "C_C") (pintype "passive"))
      (node (ref "OLI-EXP") (pin "2") (pinfunction "KL_2") (pintype "passive"))
      (node (ref "OLI-EXP") (pin "4") (pinfunction "KL_4") (pintype "passive"))
      (node (ref "OLI-EXP") (pin "8") (pinfunction "KL_8") (pintype "passive"))
      (node (ref "PMOD1/2") (pin "3") (pinfunction "3_3") (pintype "passive"))
      (node (ref "PMOD1/2") (pin "4") (pinfunction "4_4") (pintype "passive"))
      (node (ref "PMOD11/12") (pin "3") (pinfunction "3_3") (pintype "passive"))
      (node (ref "PMOD11/12") (pin "4") (pinfunction "4_4") (pintype "passive"))
      (node (ref "PMOD13") (pin "5") (pinfunction "5_5") (pintype "passive"))
      (node (ref "PMOD14") (pin "5") (pinfunction "5_5") (pintype "passive"))
      (node (ref "PMOD3/4") (pin "3") (pinfunction "3_3") (pintype "passive"))
      (node (ref "PMOD3/4") (pin "4") (pinfunction "4_4") (pintype "passive"))
      (node (ref "PMOD5/6") (pin "3") (pinfunction "3_3") (pintype "passive"))
      (node (ref "PMOD5/6") (pin "4") (pinfunction "4_4") (pintype "passive"))
      (node (ref "PMOD7/8") (pin "3") (pinfunction "3_3") (pintype "passive"))
      (node (ref "PMOD7/8") (pin "4") (pinfunction "4_4") (pintype "passive"))
      (node (ref "PMOD9/10") (pin "3") (pinfunction "3_3") (pintype "passive"))
      (node (ref "PMOD9/10") (pin "4") (pinfunction "4_4") (pintype "passive"))
      (node (ref "PWR") (pin "C") (pinfunction "C_C") (pintype "passive"))
      (node (ref "R13") (pin "1") (pinfunction "1_1") (pintype "passive"))
      (node (ref "R14") (pin "2") (pinfunction "2_2") (pintype "passive"))
      (node (ref "R22") (pin "2") (pinfunction "2_2") (pintype "passive"))
      (node (ref "R24") (pin "2") (pinfunction "2_2") (pintype "passive"))
      (node (ref "S0") (pin "1") (pinfunction "1_1") (pintype "passive"))
      (node (ref "S1") (pin "3") (pinfunction "3_3") (pintype "passive"))
      (node (ref "S1") (pin "4") (pinfunction "4_4") (pintype "passive"))
      (node (ref "S2") (pin "3") (pinfunction "3_3") (pintype "passive"))
      (node (ref "S2") (pin "4") (pinfunction "4_4") (pintype "passive"))
      (node (ref "S3") (pin "1") (pinfunction "1_1") (pintype "passive"))
      (node (ref "S4") (pin "1") (pinfunction "1_1") (pintype "passive"))
      (node (ref "SD1") (pin "6") (pinfunction "VSS_6") (pintype "power_in"))
      (node (ref "SD1") (pin "S1") (pinfunction "S1_S1") (pintype "passive"))
      (node (ref "SD1") (pin "S2") (pinfunction "S2_S2") (pintype "passive"))
      (node (ref "SD1") (pin "S3") (pinfunction "S3_S3") (pintype "passive"))
      (node (ref "SD1") (pin "S4") (pinfunction "S4_S4") (pintype "passive"))
      (node (ref "U$16") (pin "P$1") (pinfunction "P_P$1") (pintype "bidirectional"))
      (node (ref "U$2") (pin "P$5") (pinfunction "GND_P$5") (pintype "bidirectional"))
      (node (ref "U$21") (pin "P$1") (pinfunction "P_P$1") (pintype "bidirectional"))
      (node (ref "U$22") (pin "P$1") (pinfunction "P_P$1") (pintype "bidirectional"))
      (node (ref "U$24") (pin "P$1") (pinfunction "P_P$1") (pintype "bidirectional"))
      (node (ref "X1") (pin "P2") (pinfunction "GND_P2") (pintype "power_in"))
      (node (ref "Y1") (pin "2") (pinfunction "GND_2") (pintype "power_in"))
      (node (ref "Y1") (pin "4") (pinfunction "GND_4") (pintype "passive"))
      (node (ref "Y2") (pin "2") (pinfunction "GND_2") (pintype "power_in"))
      (node (ref "Y2") (pin "4") (pinfunction "GND_4") (pintype "passive"))
    )
    (net (code "161") (name "Net-(COM-D+)") (class "Default")
      (node (ref "COM") (pin "P$3") (pinfunction "D+_P$3") (pintype "bidirectional"))
      (node (ref "IC1") (pin "5") (pinfunction "D+_5") (pintype "bidirectional"))
    )
    (net (code "162") (name "Net-(COM-D-)") (class "Default")
      (node (ref "COM") (pin "P$2") (pinfunction "D-_P$2") (pintype "bidirectional"))
      (node (ref "IC1") (pin "6") (pinfunction "D-_6") (pintype "bidirectional"))
    )
    (net (code "163") (name "Net-(COM-SH3)") (class "Default")
      (node (ref "C26") (pin "2") (pinfunction "2_2") (pintype "passive"))
      (node (ref "COM") (pin "SH5") (pinfunction "SH2_SH5") (pintype "bidirectional"))
      (node (ref "COM") (pin "SH6") (pinfunction "SH4_SH6") (pintype "bidirectional"))
      (node (ref "COM") (pin "SH@2") (pinfunction "SH2_SH@2") (pintype "bidirectional"))
      (node (ref "COM") (pin "SH@3") (pinfunction "SH3_SH@3") (pintype "bidirectional"))
      (node (ref "COM") (pin "SH@4") (pinfunction "SH4_SH@4") (pintype "bidirectional"))
      (node (ref "R24") (pin "1") (pinfunction "1_1") (pintype "passive"))
    )
    (net (code "164") (name "Net-(D1-PadC)") (class "Default")
      (node (ref "D1") (pin "C") (pinfunction "C_C") (pintype "passive"))
      (node (ref "D3") (pin "C") (pinfunction "C_C") (pintype "passive"))
      (node (ref "F1") (pin "1") (pinfunction "1_1") (pintype "passive"))
    )
    (net (code "165") (name "Net-(IC1-XI)") (class "Default")
      (node (ref "C41") (pin "2") (pinfunction "2_2") (pintype "passive"))
      (node (ref "IC1") (pin "7") (pinfunction "XI_7") (pintype "bidirectional"))
      (node (ref "Y2") (pin "3") (pinfunction "X2_3") (pintype "passive"))
    )
    (net (code "166") (name "Net-(IC1-XO)") (class "Default")
      (node (ref "C40") (pin "2") (pinfunction "2_2") (pintype "passive"))
      (node (ref "IC1") (pin "8") (pinfunction "XO_8") (pintype "bidirectional"))
      (node (ref "Y2") (pin "1") (pinfunction "X1_1") (pintype "passive"))
    )
    (net (code "167") (name "Net-(IC3-GNDPLL0)") (class "Default")
      (node (ref "C36") (pin "1") (pinfunction "1_1") (pintype "passive"))
      (node (ref "IC3") (pin "53") (pinfunction "GNDPLL0_53") (pintype "bidirectional"))
    )
    (net (code "168") (name "Net-(IC3-GNDPLL1)") (class "Default")
      (node (ref "C9") (pin "1") (pinfunction "1_1") (pintype "passive"))
      (node (ref "IC3") (pin "127") (pinfunction "GNDPLL1_127") (pintype "bidirectional"))
    )
    (net (code "169") (name "Net-(IC3-VCCPLL0)") (class "Default")
      (node (ref "C36") (pin "2") (pinfunction "2_2") (pintype "passive"))
      (node (ref "IC3") (pin "54") (pinfunction "VCCPLL0_54") (pintype "bidirectional"))
      (node (ref "R38") (pin "1") (pinfunction "1_1") (pintype "passive"))
    )
    (net (code "170") (name "Net-(IC3-VCCPLL1)") (class "Default")
      (node (ref "C9") (pin "2") (pinfunction "2_2") (pintype "passive"))
      (node (ref "IC3") (pin "126") (pinfunction "VCCPLL1_126") (pintype "bidirectional"))
      (node (ref "R39") (pin "2") (pinfunction "2_2") (pintype "passive"))
    )
    (net (code "171") (name "Net-(IC4-PD0_OSC_IN)") (class "Default")
      (node (ref "C27") (pin "2") (pinfunction "2_2") (pintype "passive"))
      (node (ref "IC4") (pin "5") (pinfunction "PD0_OSC_IN_5") (pintype "input"))
      (node (ref "Y1") (pin "1") (pinfunction "X1_1") (pintype "passive"))
    )
    (net (code "172") (name "Net-(IC4-PD1_OSC_OUT)") (class "Default")
      (node (ref "C34") (pin "2") (pinfunction "2_2") (pintype "passive"))
      (node (ref "IC4") (pin "6") (pinfunction "PD1_OSC_OUT_6") (pintype "output"))
      (node (ref "Y1") (pin "3") (pinfunction "X2_3") (pintype "passive"))
    )
    (net (code "173") (name "Net-(IC7-EN)") (class "Default")
      (node (ref "C62") (pin "2") (pinfunction "2_2") (pintype "passive"))
      (node (ref "IC7") (pin "3") (pinfunction "EN_3") (pintype "input"))
      (node (ref "R28") (pin "2") (pinfunction "2_2") (pintype "passive"))
    )
    (net (code "174") (name "Net-(LED5-PadC)") (class "Default")
      (node (ref "LED5") (pin "C") (pinfunction "C_C") (pintype "passive"))
      (node (ref "R5") (pin "2") (pinfunction "2_2") (pintype "passive"))
    )
    (net (code "175") (name "Net-(LED6-PadC)") (class "Default")
      (node (ref "LED6") (pin "C") (pinfunction "C_C") (pintype "passive"))
      (node (ref "R26") (pin "2") (pinfunction "2_2") (pintype "passive"))
    )
    (net (code "176") (name "Net-(OLI-EXPAE-KL)") (class "Default")
      (node (ref "OLI-EXP") (pin "6") (pinfunction "KL_6") (pintype "passive"))
      (node (ref "R43") (pin "2") (pinfunction "2_2") (pintype "passive"))
    )
    (net (code "177") (name "Net-(PWR-PadA)") (class "Default")
      (node (ref "PWR") (pin "A") (pinfunction "A_A") (pintype "passive"))
      (node (ref "R6") (pin "2") (pinfunction "2_2") (pintype "passive"))
    )
    (net (code "178") (name "Net-(U$2-SH3)") (class "Default")
      (node (ref "C39") (pin "2") (pinfunction "2_2") (pintype "passive"))
      (node (ref "R22") (pin "1") (pinfunction "1_1") (pintype "passive"))
      (node (ref "U$2") (pin "SH5") (pinfunction "SH2_SH5") (pintype "bidirectional"))
      (node (ref "U$2") (pin "SH6") (pinfunction "SH4_SH6") (pintype "bidirectional"))
      (node (ref "U$2") (pin "SH@2") (pinfunction "SH2_SH@2") (pintype "bidirectional"))
      (node (ref "U$2") (pin "SH@3") (pinfunction "SH3_SH@3") (pintype "bidirectional"))
      (node (ref "U$2") (pin "SH@4") (pinfunction "SH4_SH@4") (pintype "bidirectional"))
    )
    (net (code "179") (name "Net-(X1-OUT)") (class "Default")
      (node (ref "R43") (pin "1") (pinfunction "1_1") (pintype "passive"))
      (node (ref "R44") (pin "1") (pinfunction "1_1") (pintype "passive"))
      (node (ref "X1") (pin "P3") (pinfunction "OUT_P3") (pintype "output"))
    )
    (net (code "180") (name "VCC") (class "Default")
      (node (ref "C12") (pin "1") (pinfunction "1_1") (pintype "passive"))
      (node (ref "C14") (pin "1") (pinfunction "1_1") (pintype "passive"))
      (node (ref "C19") (pin "1") (pinfunction "1_1") (pintype "passive"))
      (node (ref "C24") (pin "2") (pinfunction "2_2") (pintype "passive"))
      (node (ref "C35") (pin "1") (pinfunction "1_1") (pintype "passive"))
      (node (ref "C55") (pin "1") (pinfunction "1_1") (pintype "passive"))
      (node (ref "C57") (pin "1") (pinfunction "1_1") (pintype "passive"))
      (node (ref "IC3") (pin "111") (pinfunction "VCC_111") (pintype "bidirectional"))
      (node (ref "IC3") (pin "27") (pinfunction "VCC_27") (pintype "bidirectional"))
      (node (ref "IC3") (pin "40") (pinfunction "VCC_40") (pintype "bidirectional"))
      (node (ref "IC3") (pin "92") (pinfunction "VCC_92") (pintype "bidirectional"))
      (node (ref "IC7") (pin "5") (pinfunction "VOUT_5") (pintype "power_in"))
      (node (ref "R38") (pin "2") (pinfunction "2_2") (pintype "passive"))
      (node (ref "R39") (pin "1") (pinfunction "1_1") (pintype "passive"))
      (node (ref "VCC") (pin "TP") (pinfunction "TP_TP") (pintype "input"))
    )
    (net (code "181") (name "unconnected-(COM-ID-PadP$4)") (class "Default")
      (node (ref "COM") (pin "P$4") (pinfunction "ID_P$4") (pintype "bidirectional"))
    )
    (net (code "182") (name "unconnected-(COM-SH1-PadSH@1)") (class "Default")
      (node (ref "COM") (pin "SH@1") (pinfunction "SH1_SH@1") (pintype "bidirectional"))
    )
    (net (code "183") (name "unconnected-(COMS-Pad1)") (class "Default")
      (node (ref "COMS") (pin "1") (pinfunction "1_1") (pintype "passive"))
    )
    (net (code "184") (name "unconnected-(COMS-Pad17)") (class "Default")
      (node (ref "COMS") (pin "17") (pinfunction "17_17") (pintype "passive"))
    )
    (net (code "185") (name "unconnected-(COMS-Pad26)") (class "Default")
      (node (ref "COMS") (pin "26") (pinfunction "26_26") (pintype "passive"))
    )
    (net (code "186") (name "unconnected-(DIGITAL2-Pad8)") (class "Default")
      (node (ref "DIGITAL2") (pin "8") (pinfunction "8_8") (pintype "passive"))
    )
    (net (code "187") (name "unconnected-(IC1-DCD-Pad12)") (class "Default")
      (node (ref "IC1") (pin "12") (pinfunction "DCD_12") (pintype "bidirectional"))
    )
    (net (code "188") (name "unconnected-(IC1-DSR-Pad10)") (class "Default")
      (node (ref "IC1") (pin "10") (pinfunction "DSR_10") (pintype "bidirectional"))
    )
    (net (code "189") (name "unconnected-(IC1-DTR-Pad13)") (class "Default")
      (node (ref "IC1") (pin "13") (pinfunction "DTR_13") (pintype "bidirectional"))
    )
    (net (code "190") (name "unconnected-(IC1-RI-Pad11)") (class "Default")
      (node (ref "IC1") (pin "11") (pinfunction "RI_11") (pintype "bidirectional"))
    )
    (net (code "191") (name "unconnected-(IC1-RS232-Pad15)") (class "Default")
      (node (ref "IC1") (pin "15") (pinfunction "RS232_15") (pintype "bidirectional"))
    )
    (net (code "192") (name "unconnected-(IC2-NC-Pad28)") (class "Default")
      (node (ref "IC2") (pin "28") (pinfunction "NC_28") (pintype "no_connect"))
    )
    (net (code "193") (name "unconnected-(IC3-NC-Pad35)") (class "Default")
      (node (ref "IC3") (pin "35") (pinfunction "NC_35") (pintype "bidirectional"))
    )
    (net (code "194") (name "unconnected-(IC3-NC-Pad36)") (class "Default")
      (node (ref "IC3") (pin "36") (pinfunction "NC_36") (pintype "bidirectional"))
    )
    (net (code "195") (name "unconnected-(IC3-NC-Pad50)") (class "Default")
      (node (ref "IC3") (pin "50") (pinfunction "NC_50") (pintype "bidirectional"))
    )
    (net (code "196") (name "unconnected-(IC3-NC-Pad51)") (class "Default")
      (node (ref "IC3") (pin "51") (pinfunction "NC_51") (pintype "bidirectional"))
    )
    (net (code "197") (name "unconnected-(IC3-NC-Pad58)") (class "Default")
      (node (ref "IC3") (pin "58") (pinfunction "NC_58") (pintype "bidirectional"))
    )
    (net (code "198") (name "unconnected-(IC3-NC-Pad77)") (class "Default")
      (node (ref "IC3") (pin "77") (pinfunction "NC_77") (pintype "bidirectional"))
    )
    (net (code "199") (name "unconnected-(IC3-NC-Pad133)") (class "Default")
      (node (ref "IC3") (pin "133") (pinfunction "NC_133") (pintype "bidirectional"))
    )
    (net (code "200") (name "unconnected-(IC3-VPP_FAST-Pad109)") (class "Default")
      (node (ref "IC3") (pin "109") (pinfunction "VPP_FAST_109") (pintype "bidirectional"))
    )
    (net (code "201") (name "unconnected-(IC7-NC-Pad4)") (class "Default")
      (node (ref "IC7") (pin "4") (pinfunction "NC_4") (pintype "no_connect"))
    )
    (net (code "202") (name "unconnected-(SD1-~{CARD}-Pad9)") (class "Default")
      (node (ref "SD1") (pin "9") (pinfunction "~{CARD}_9") (pintype "passive"))
    )
    (net (code "203") (name "unconnected-(U$2-ID-PadP$4)") (class "Default")
      (node (ref "U$2") (pin "P$4") (pinfunction "ID_P$4") (pintype "bidirectional"))
    )
    (net (code "204") (name "unconnected-(U$2-SH1-PadSH@1)") (class "Default")
      (node (ref "U$2") (pin "SH@1") (pinfunction "SH1_SH@1") (pintype "bidirectional"))
    )
  )
)
